# 000018_PGKB_Rev_1_00.net
KiCad netlist of a schematic drawn in EAGLE
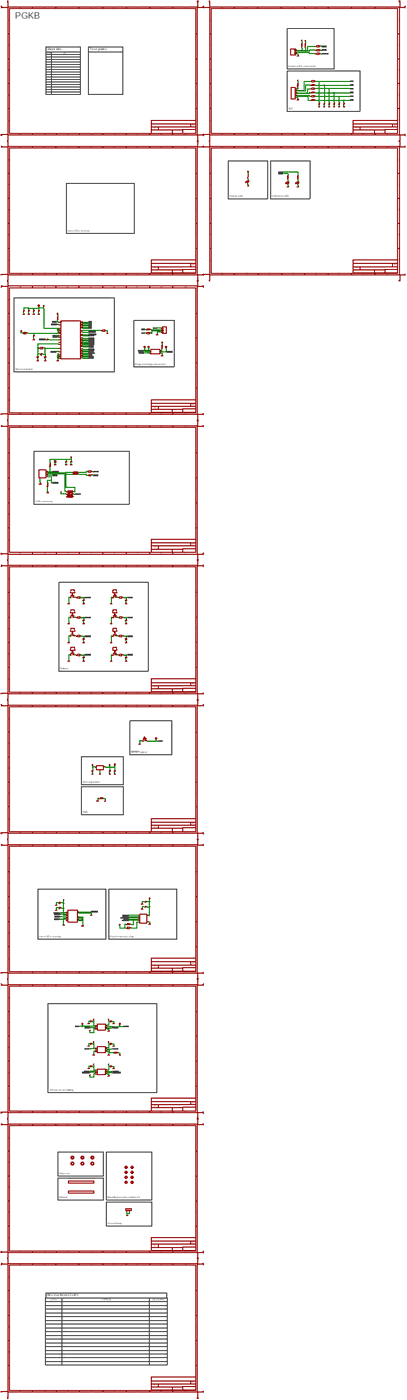
[diagram p0: schematic, sheet 1, overview]
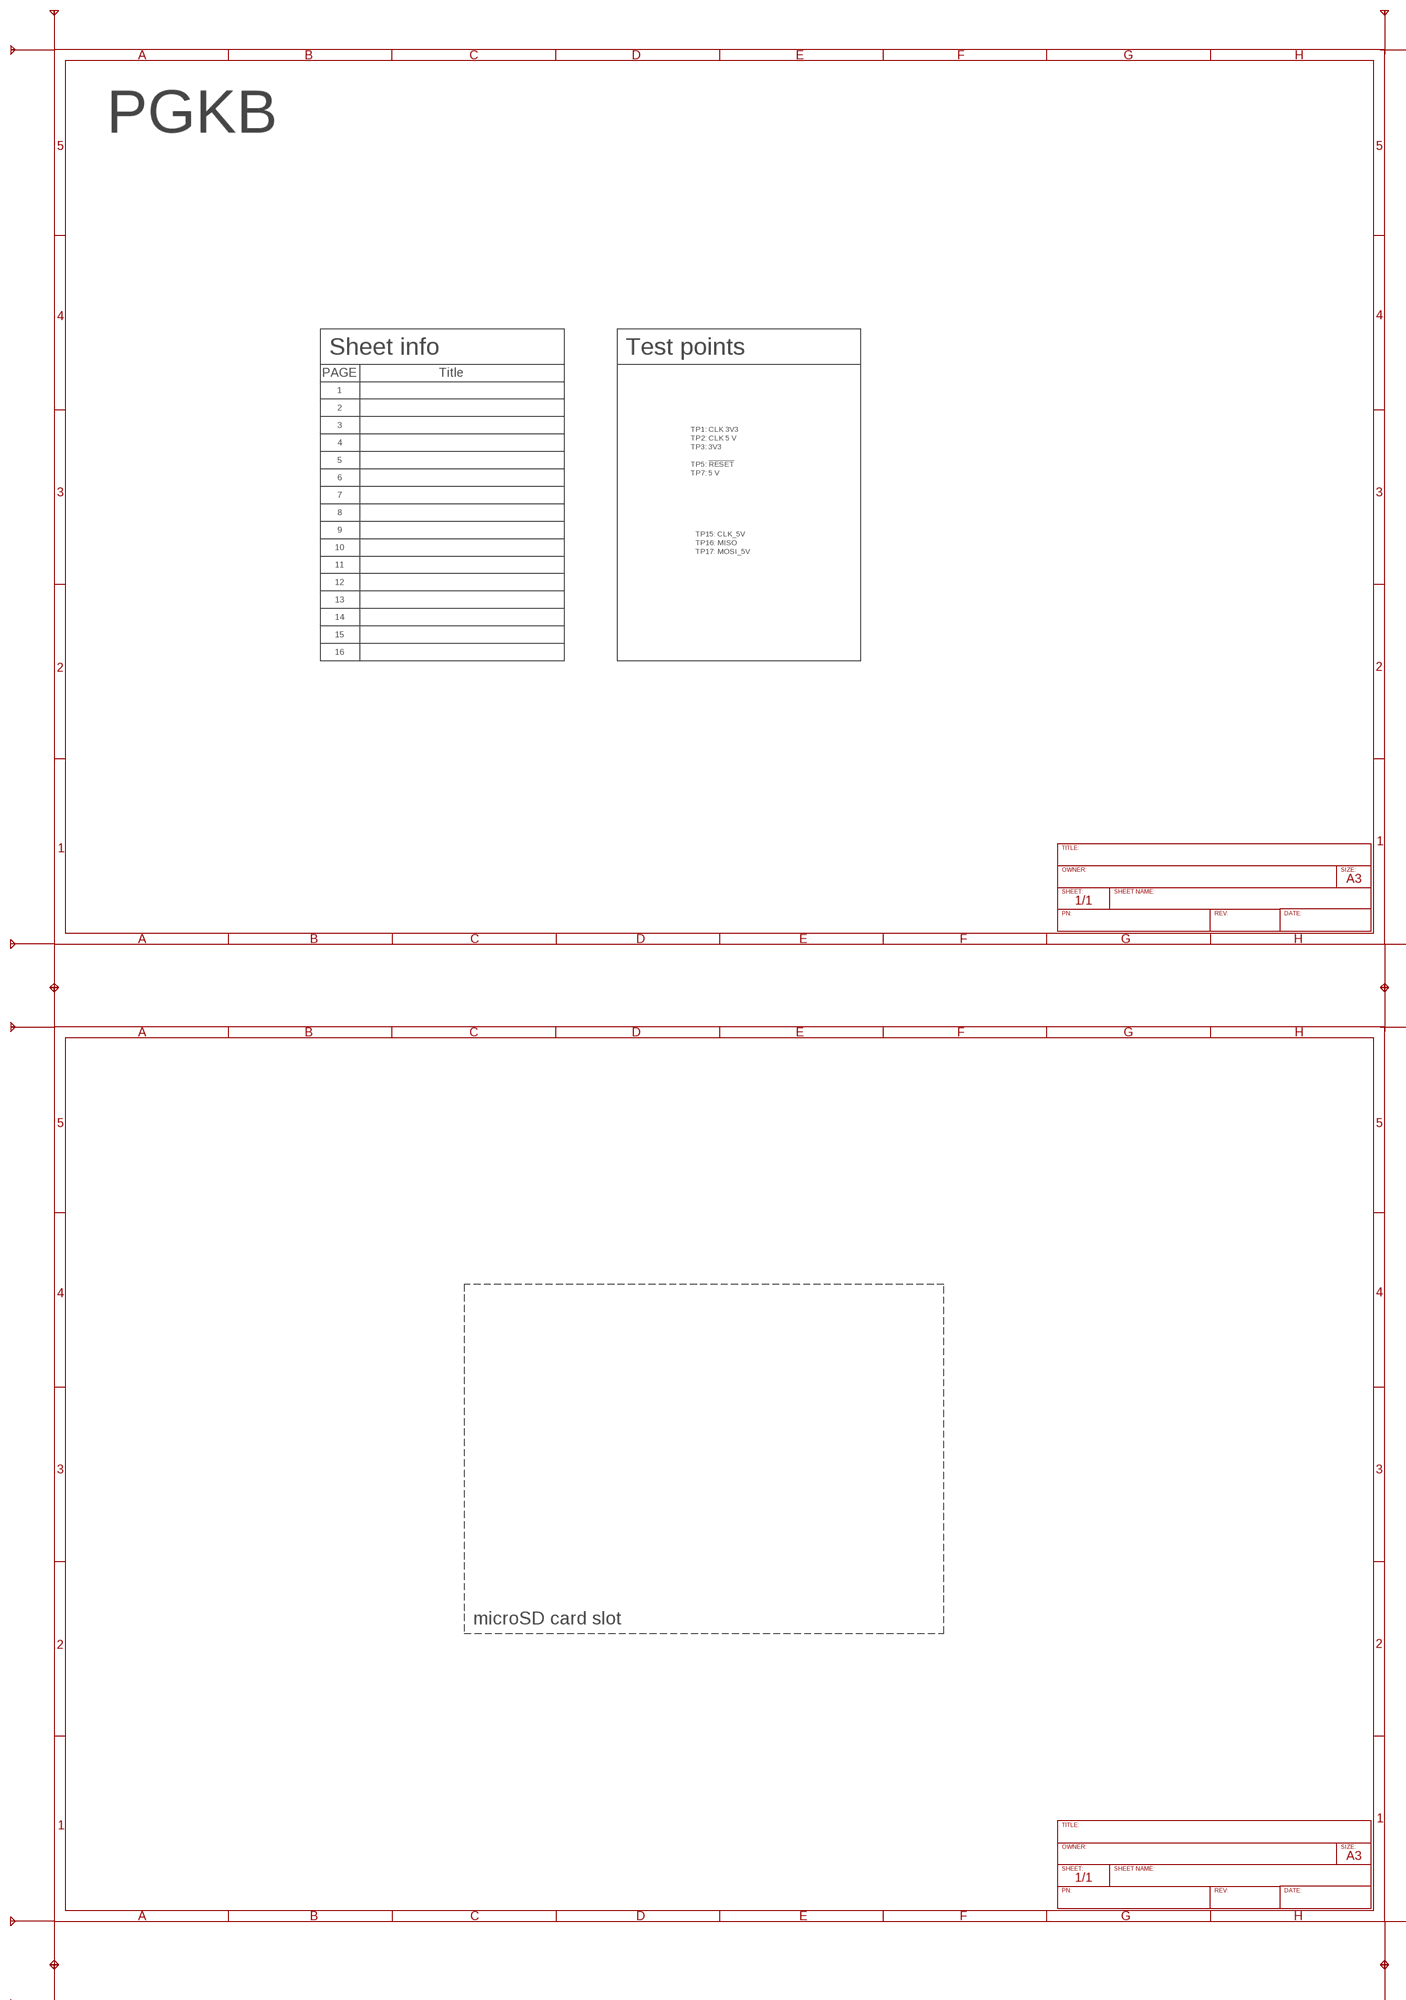
[diagram p1: schematic, sheet 1, part 1 of 7]
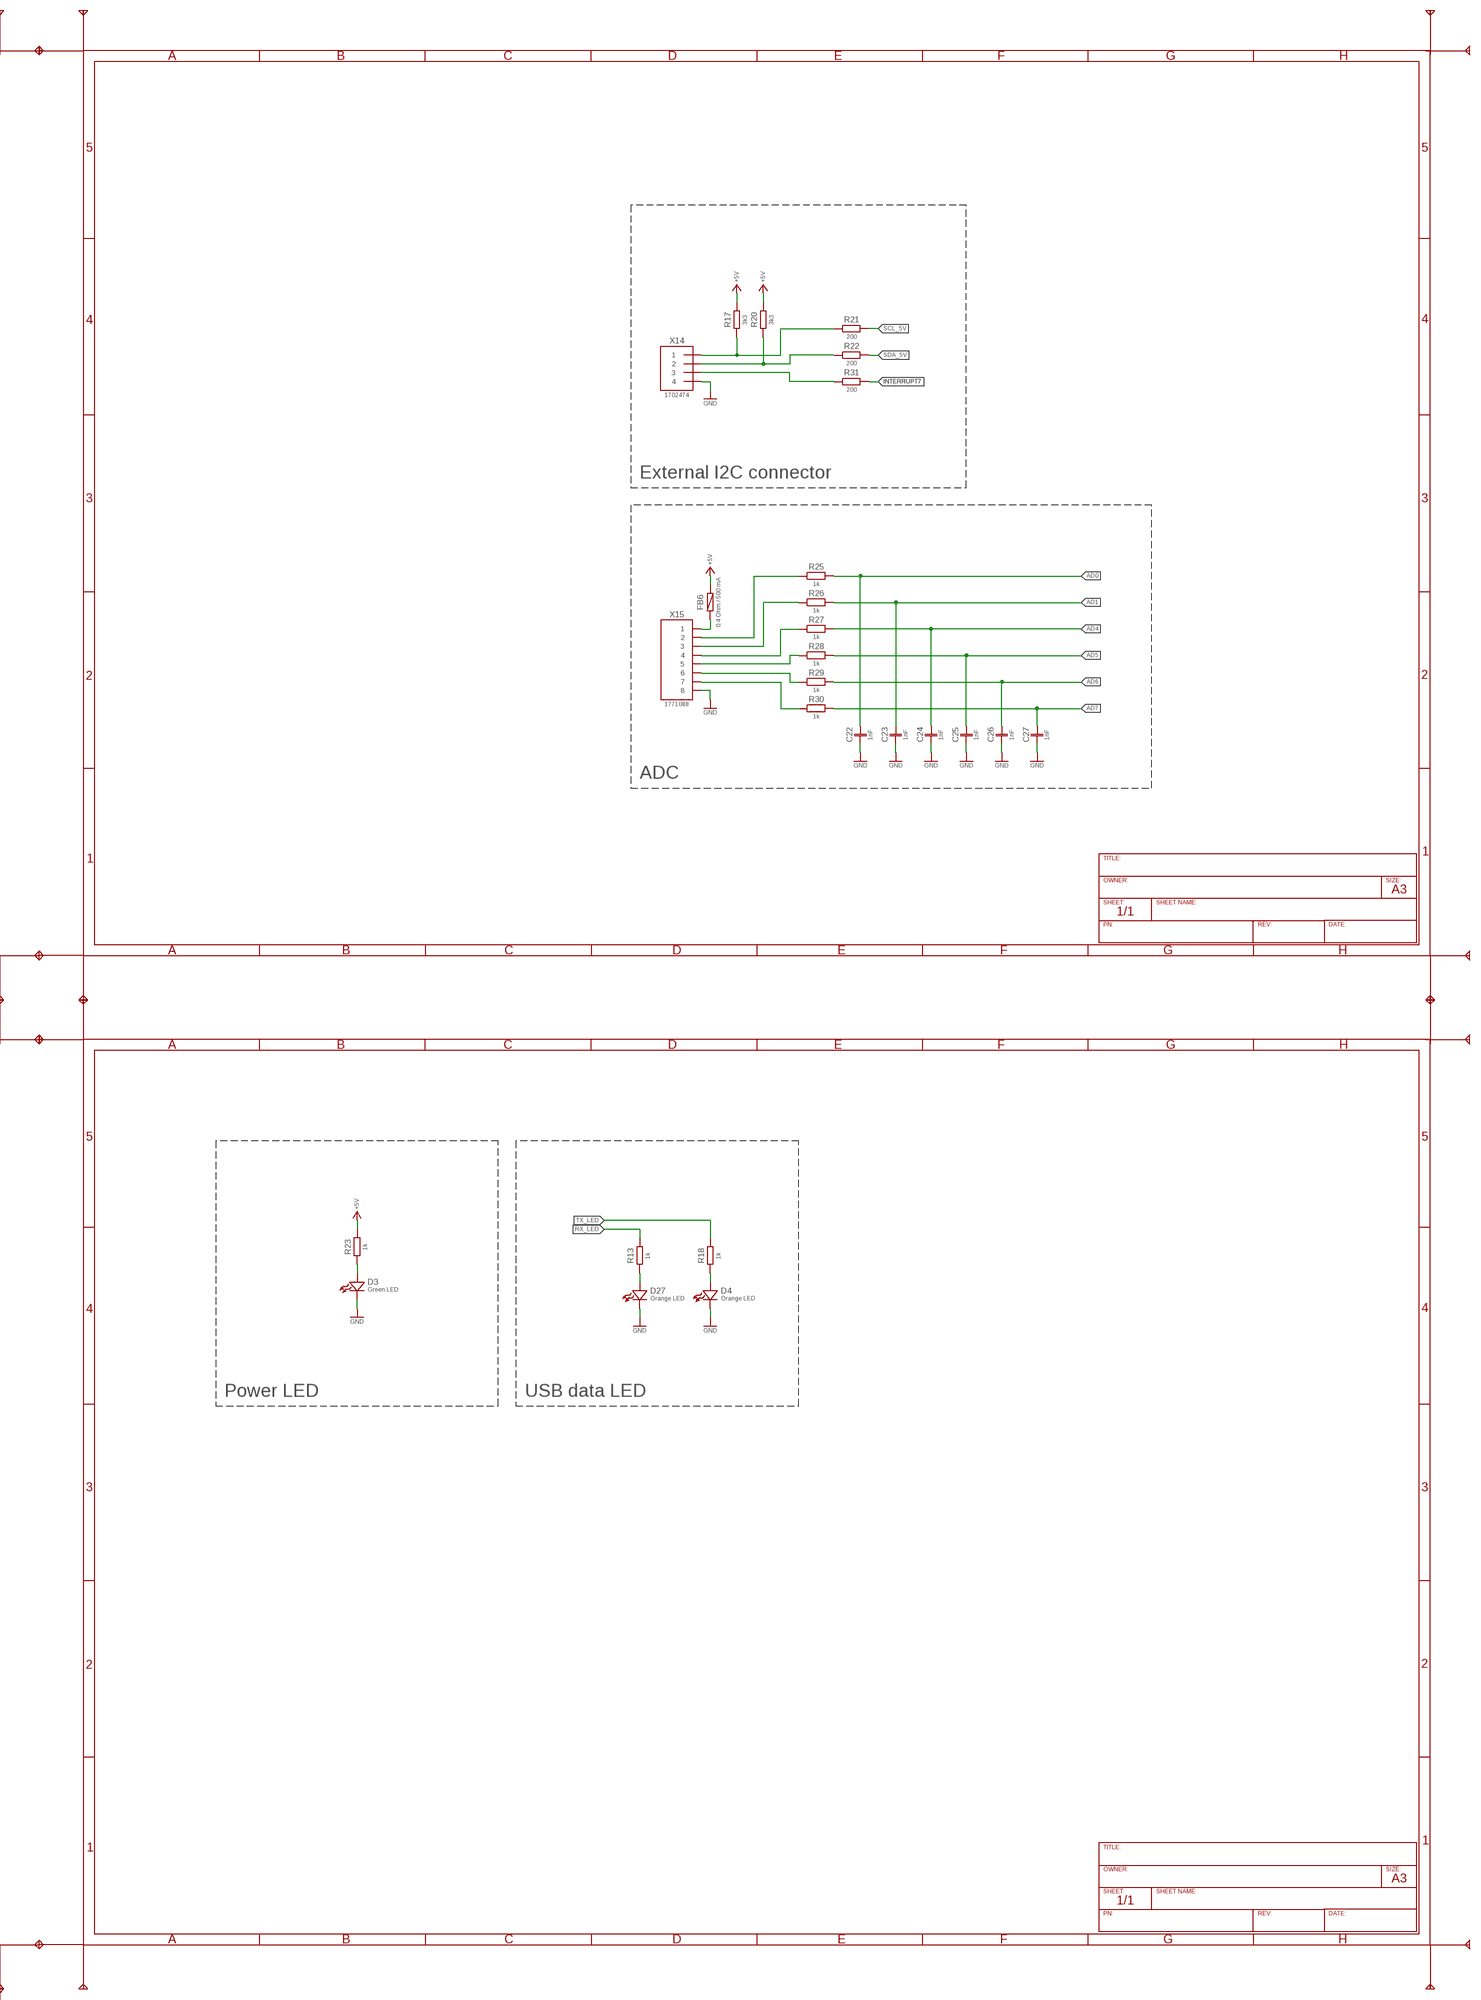
[diagram p2: schematic, sheet 1, part 2 of 7]
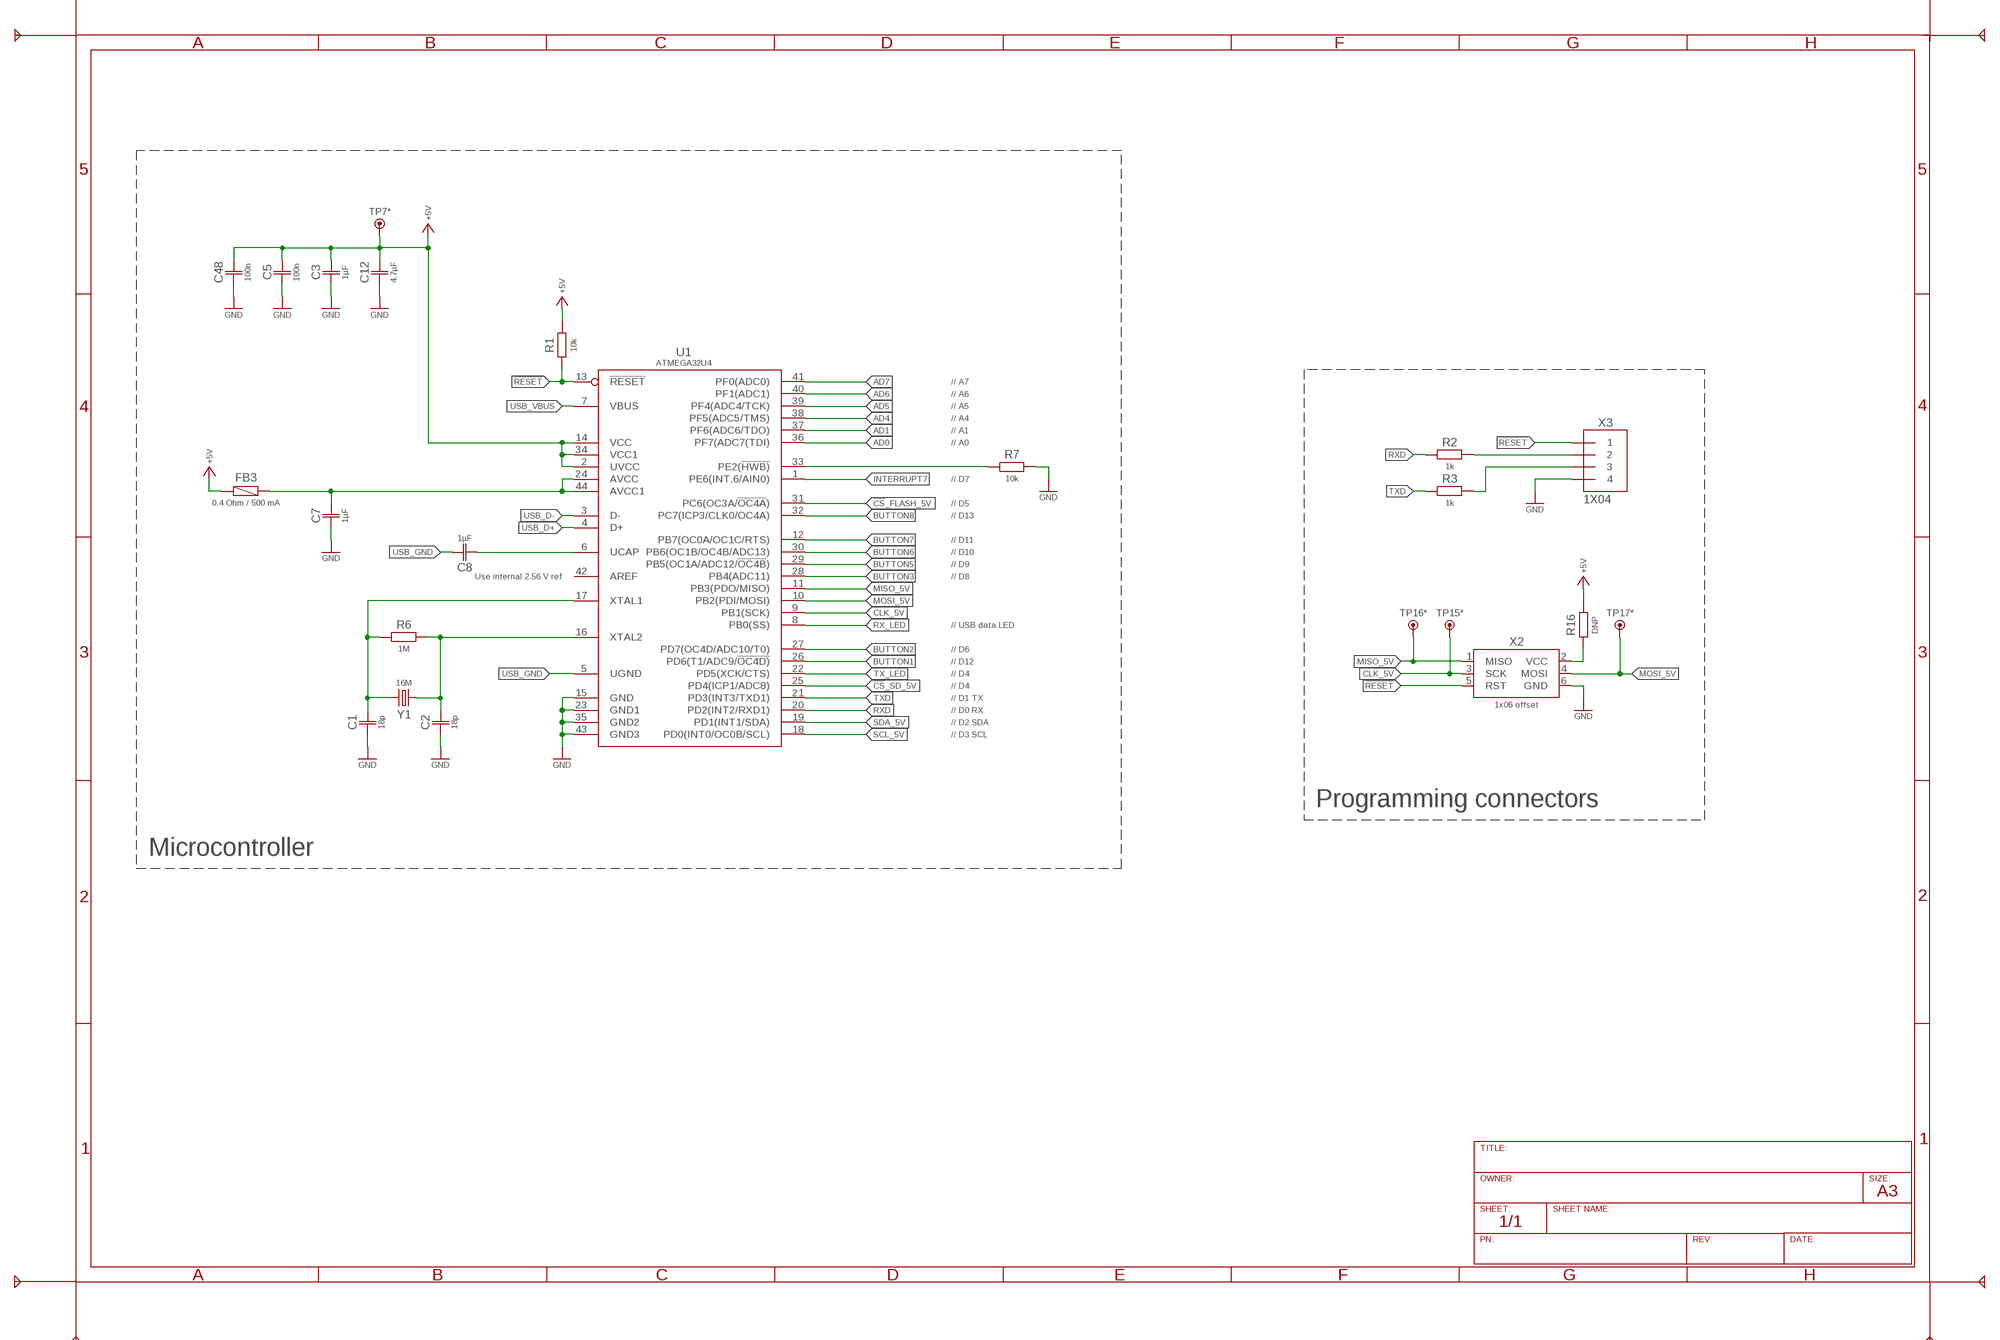
[diagram p3: schematic, sheet 1, part 3 of 7]
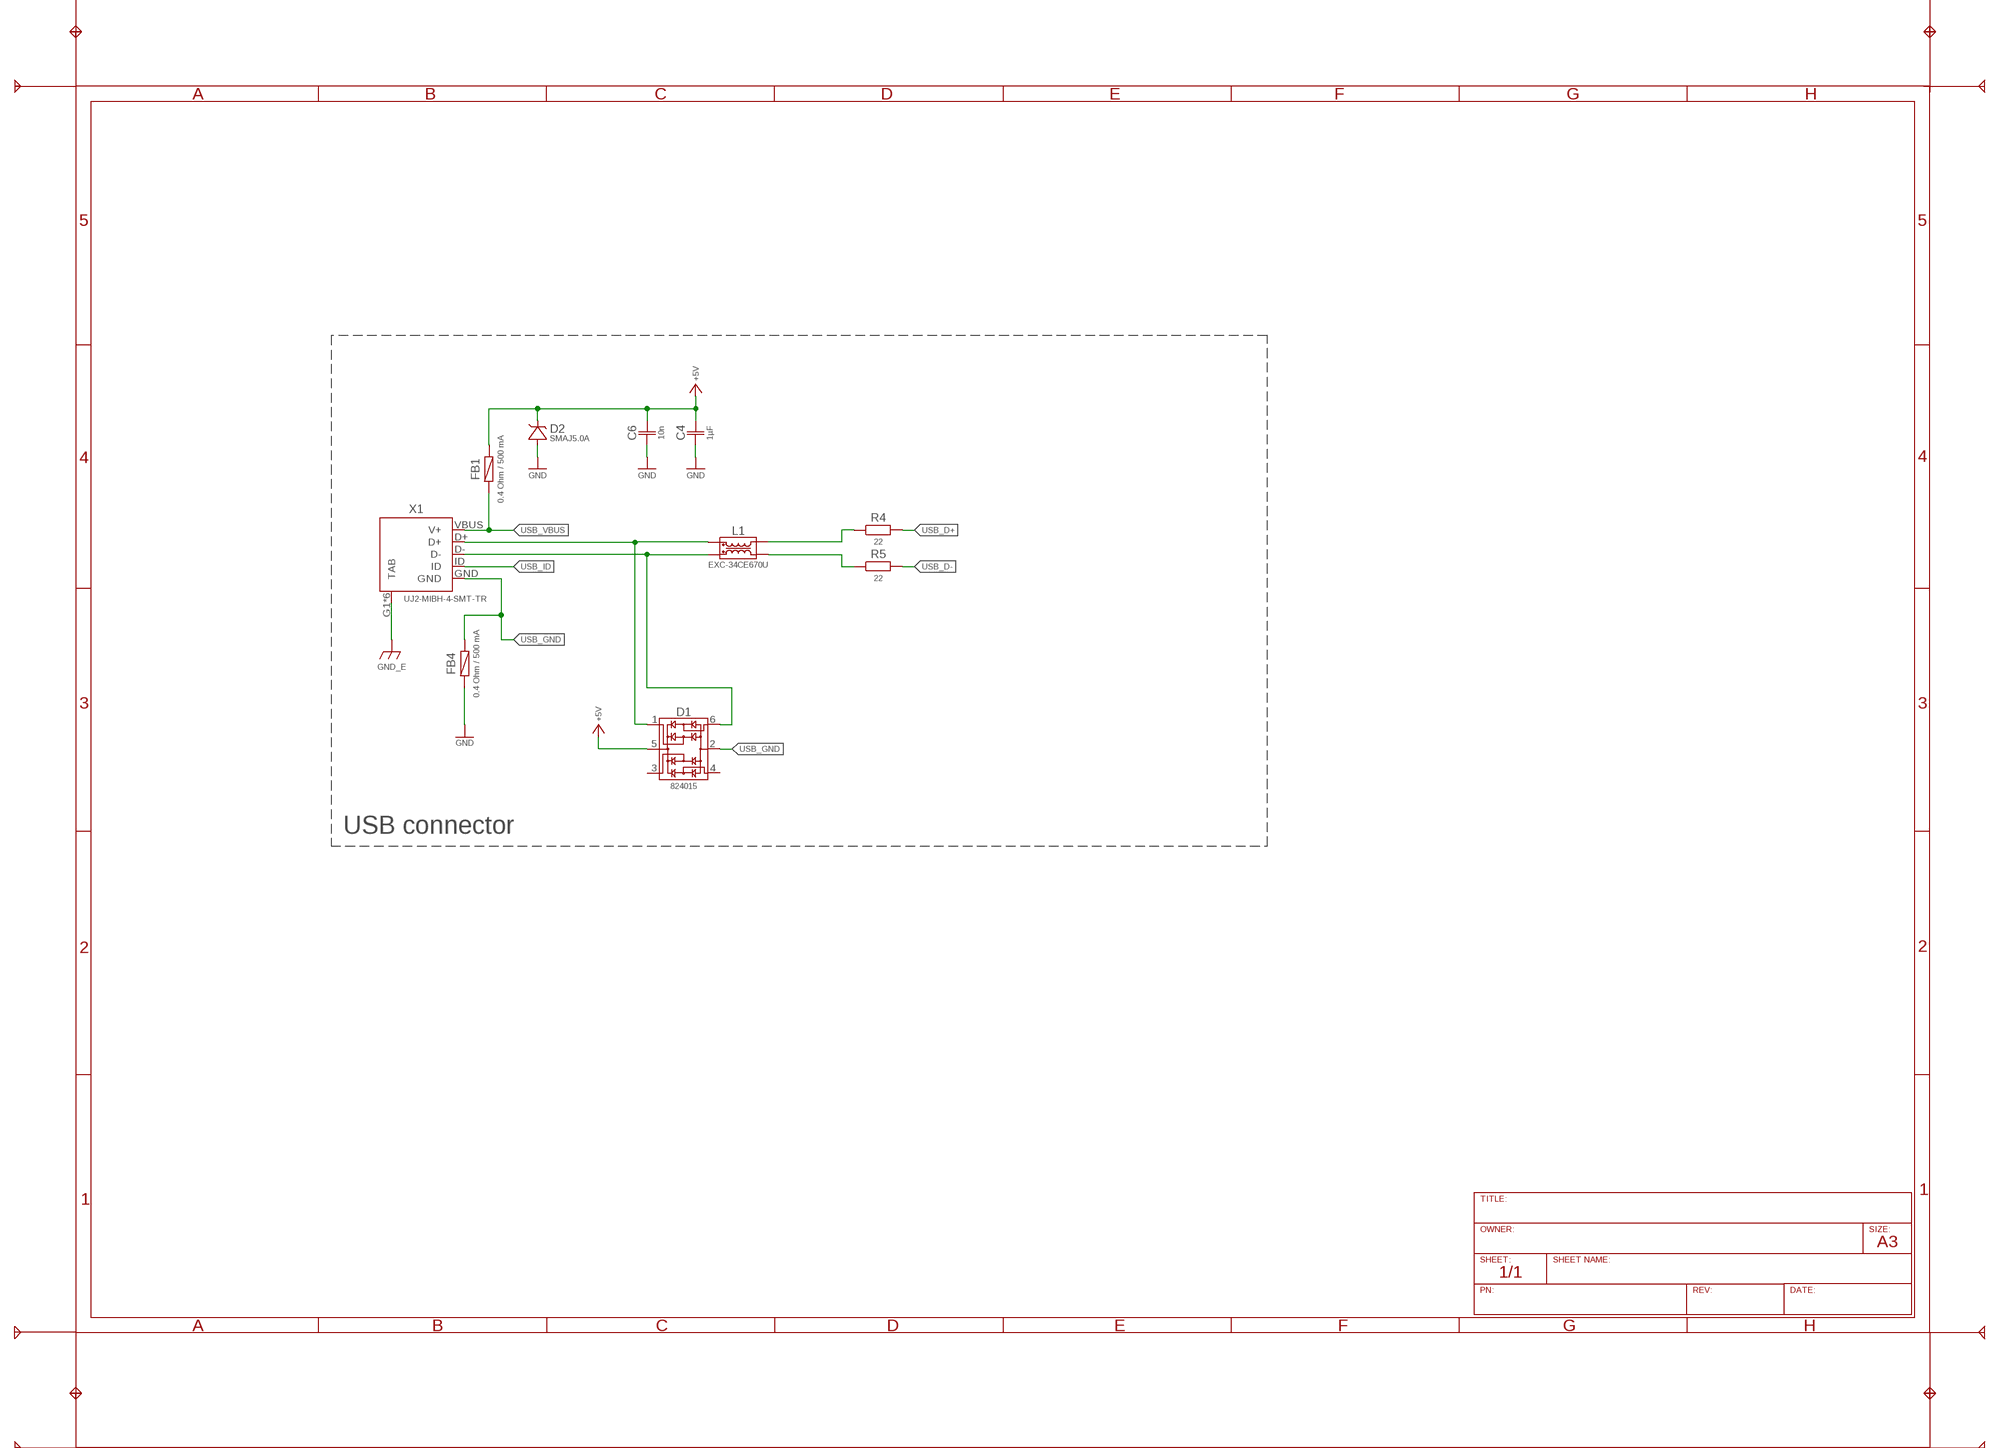
[diagram p4: schematic, sheet 1, part 4 of 7]
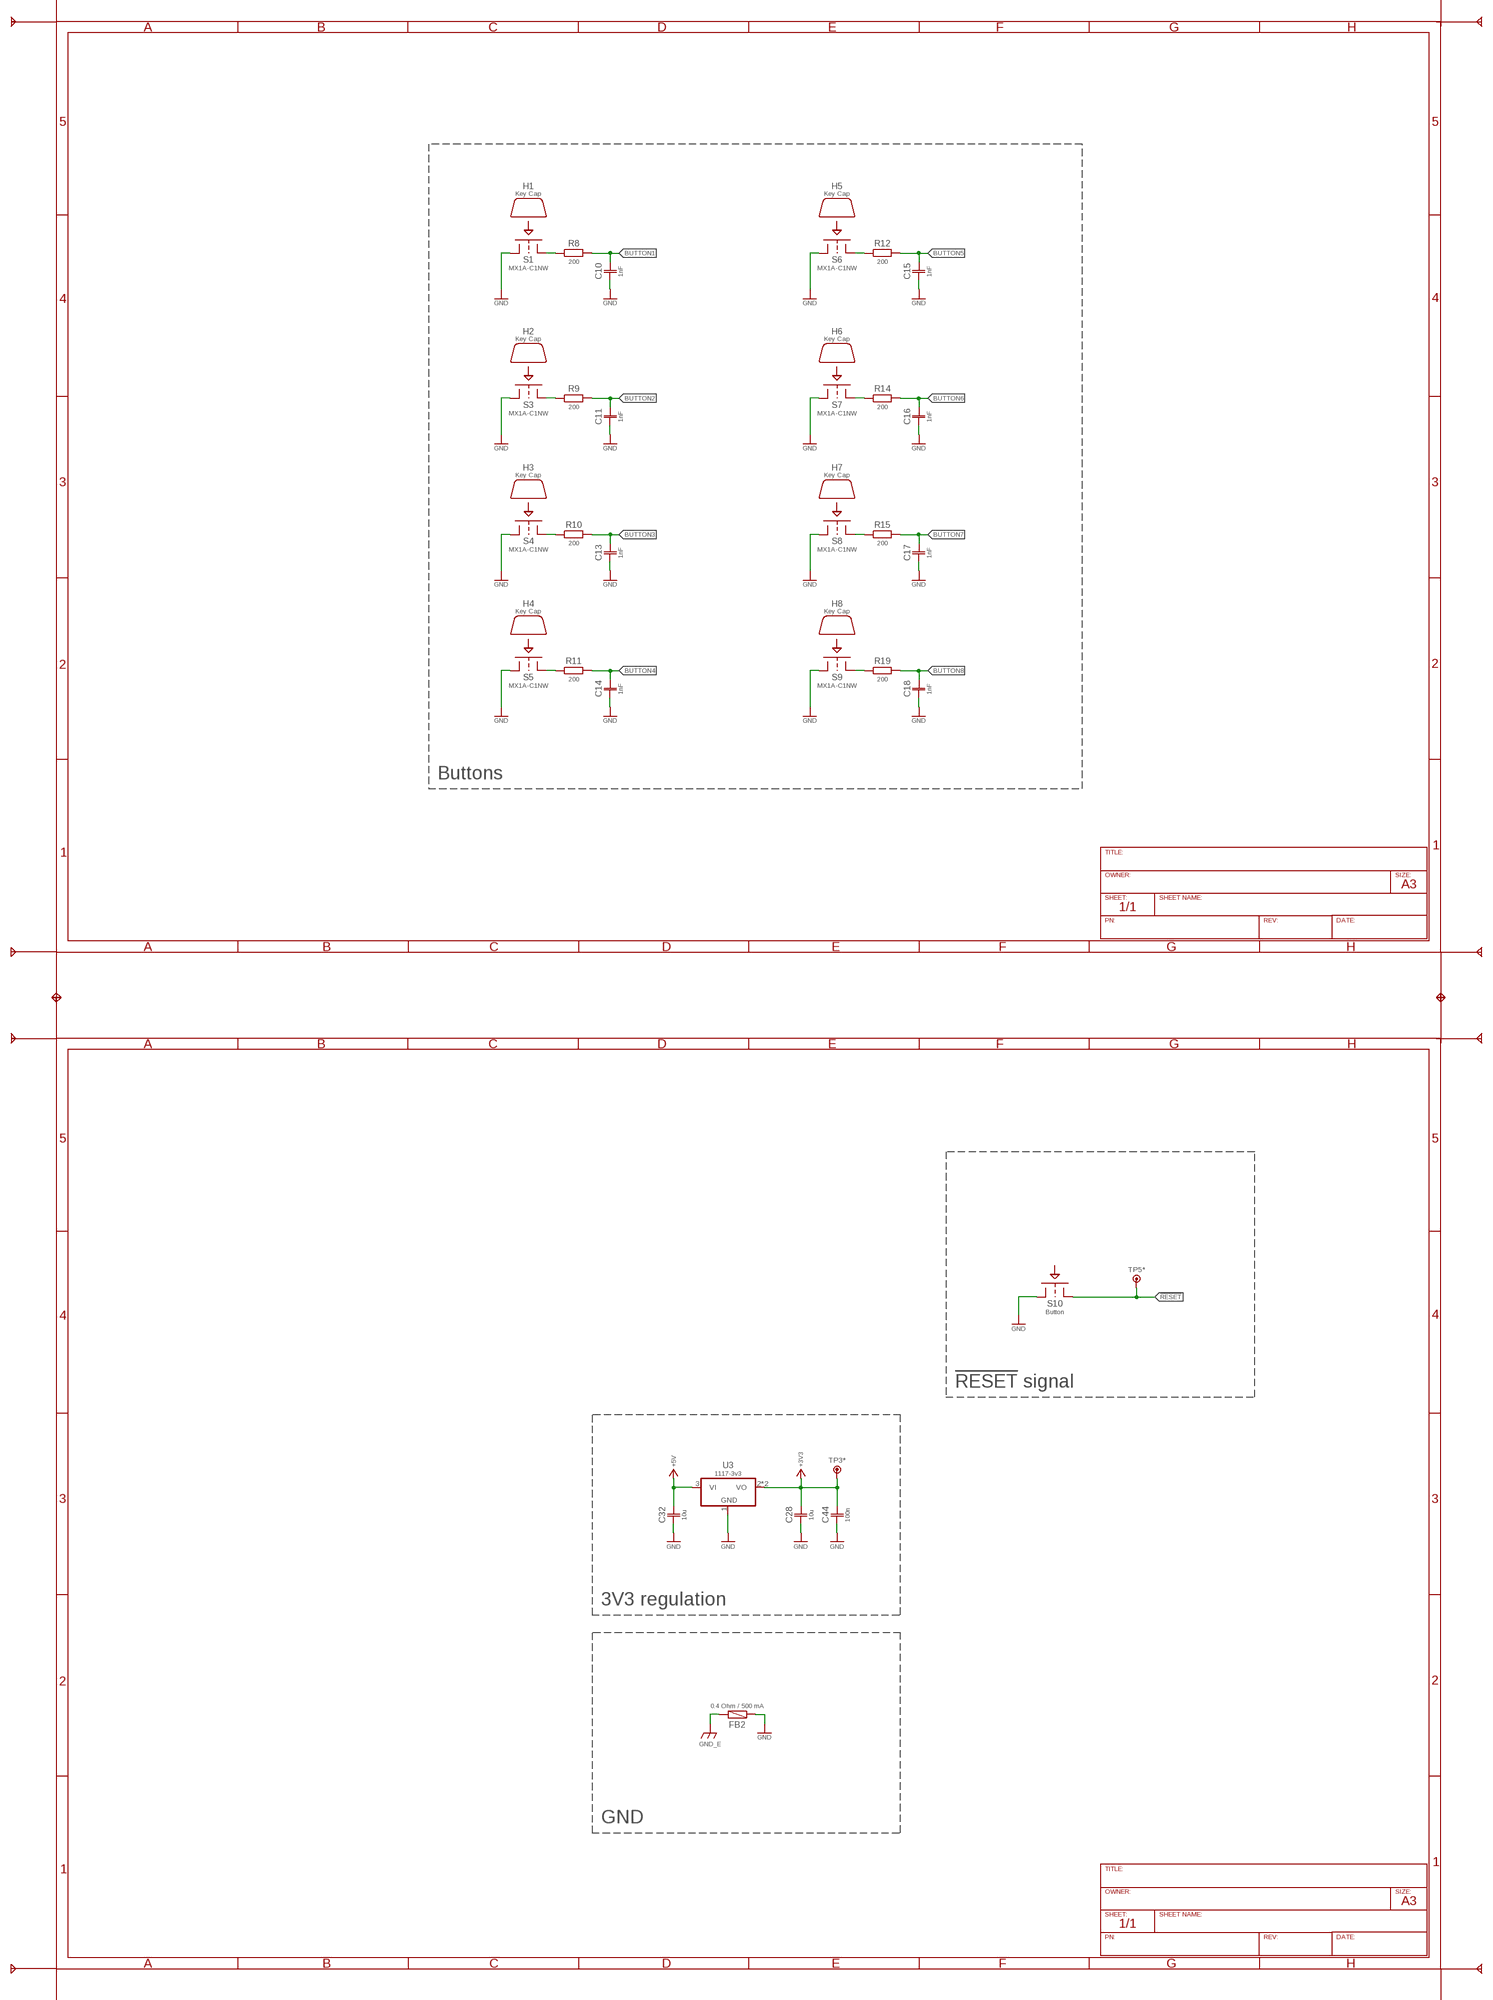
[diagram p5: schematic, sheet 1, part 5 of 7]
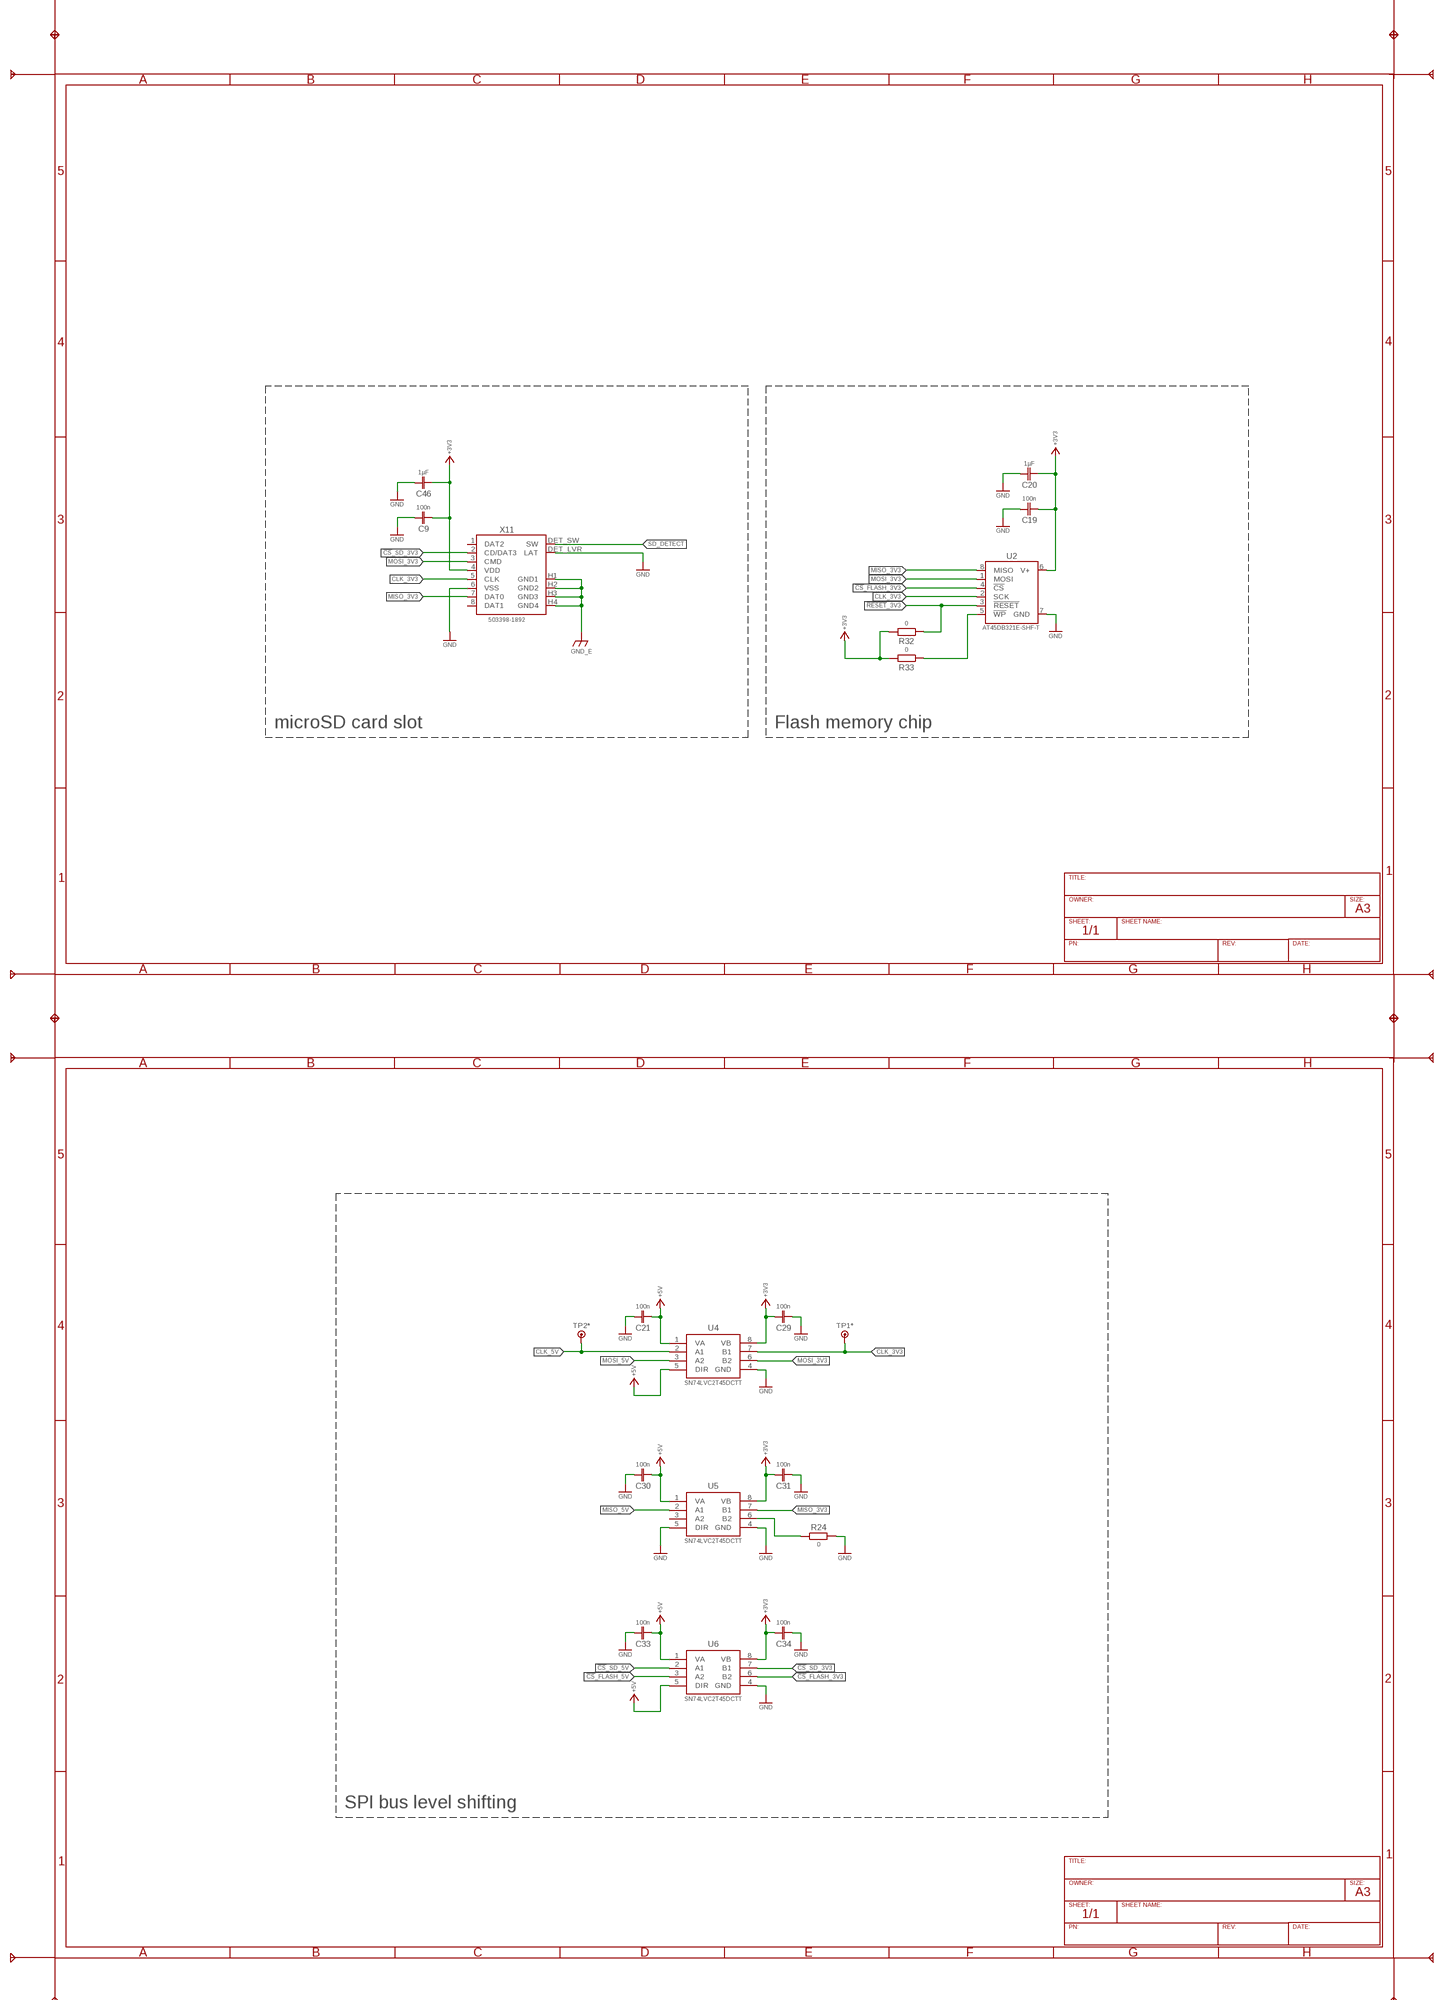
[diagram p6: schematic, sheet 1, part 6 of 7]
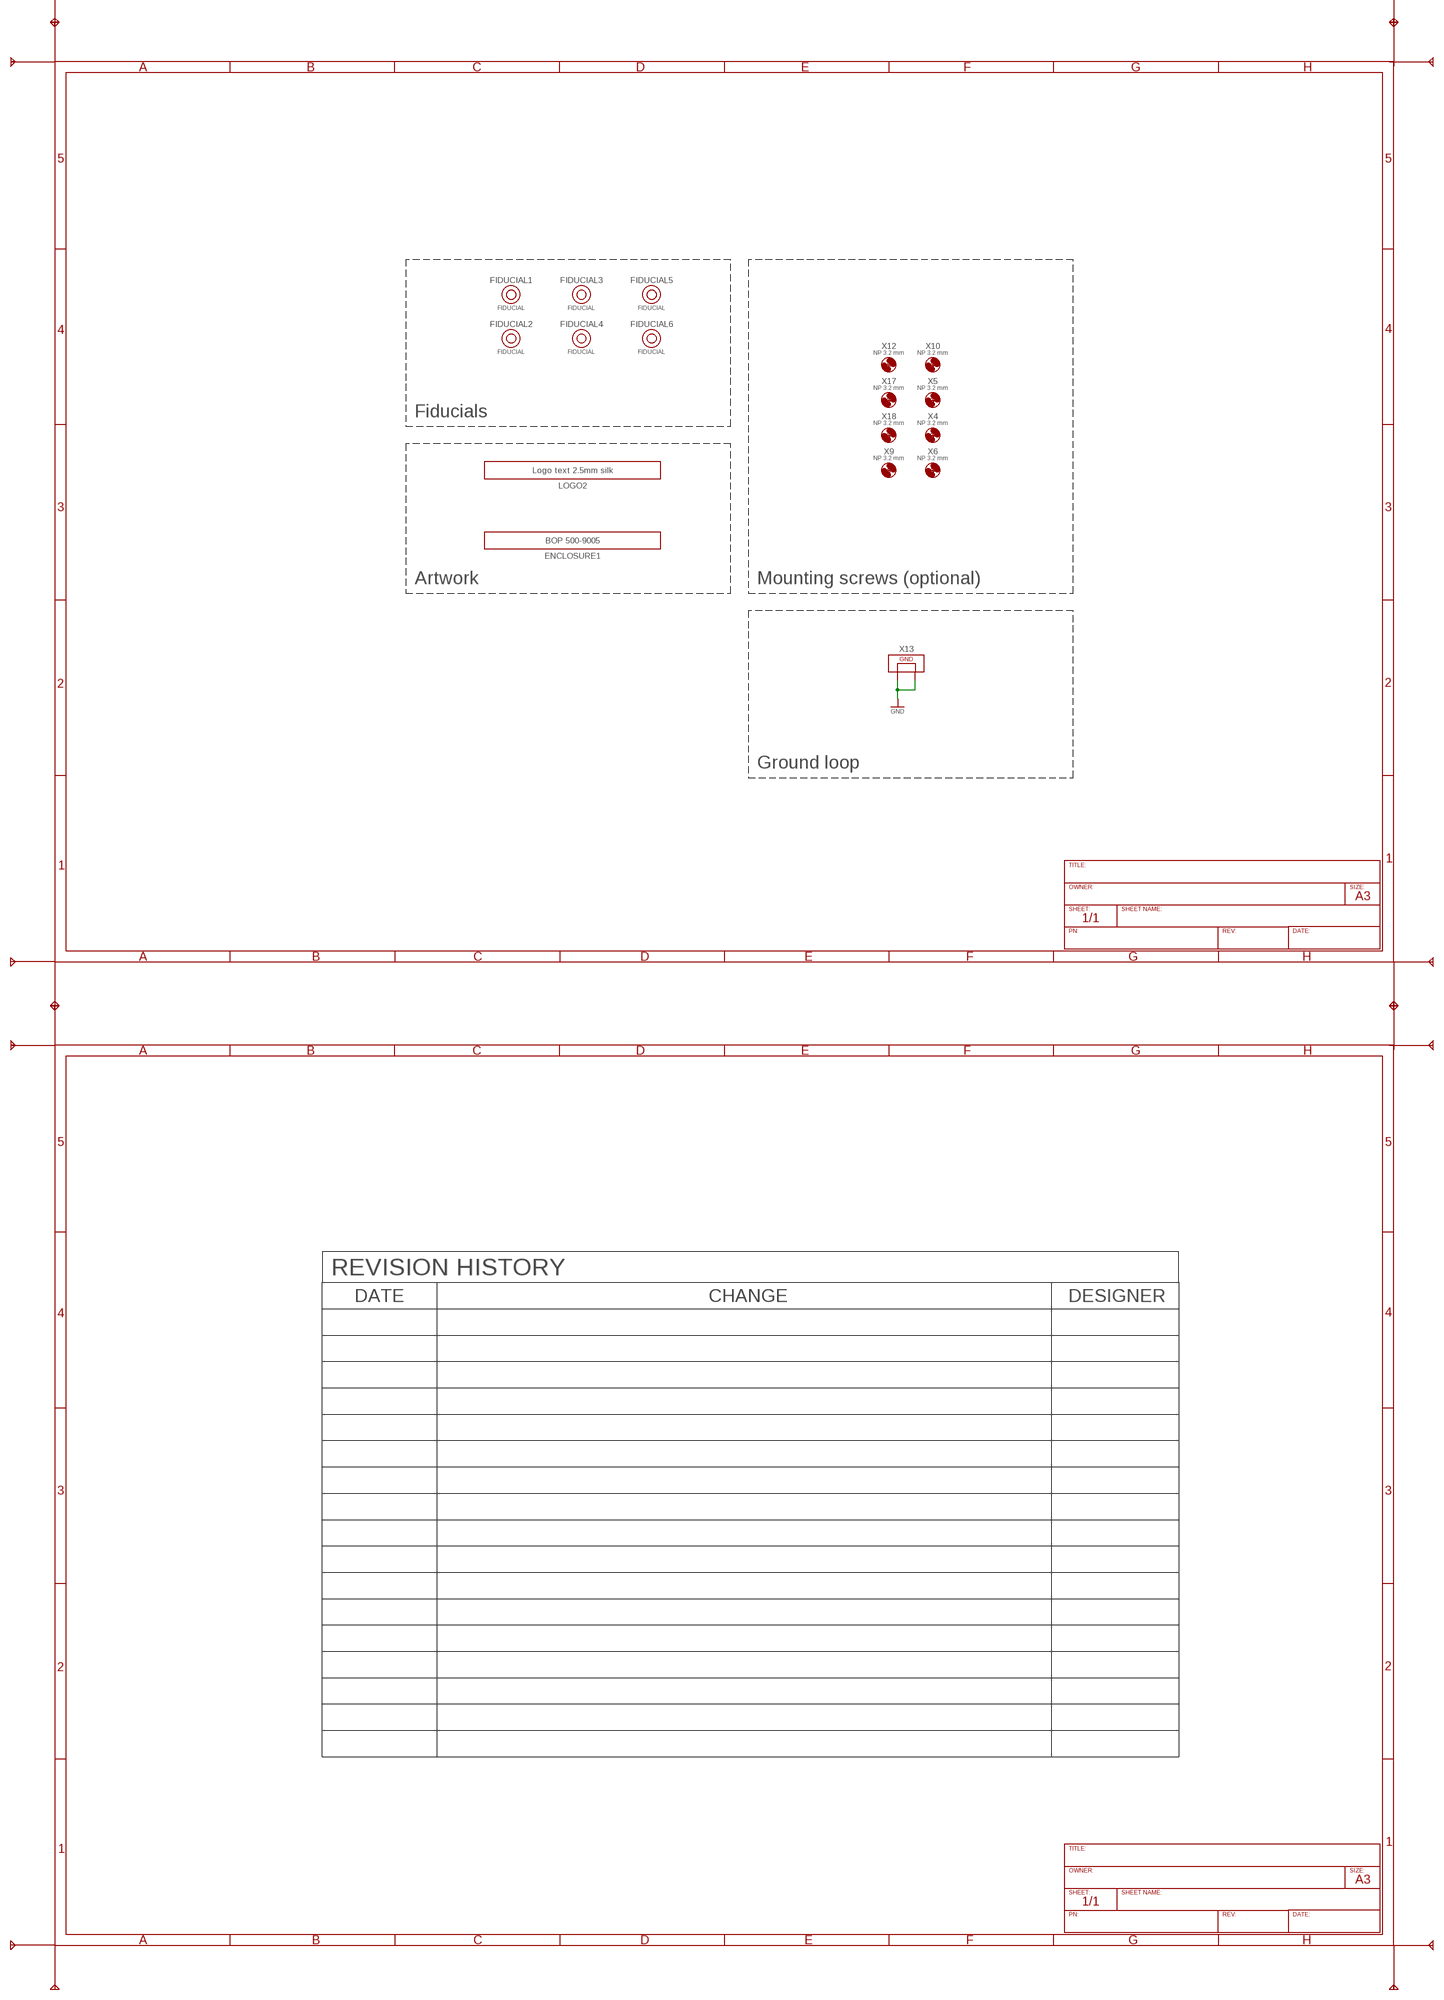
[diagram p7: schematic, sheet 1, part 7 of 7]

(export (version "E")
  (design (tool "Eeschema 10.0.6"))
  (components
    (comp (ref "C1")
      (value "C0805_18PF_50V_NP0")
      (footprint "eagle-import:CAPC2012X160")
      (fields
        (field (name "CODE") "18p")
        (field (name "MANUFACTURER") "Samsung")
        (field (name "MFG_PARTNO") "CL21C180JBANNNC")
      )
      (libsource (lib "eagle-import") (part "C0805_18PF_50V_NP0"))
    )
    (comp (ref "C2")
      (value "C0805_18PF_50V_NP0")
      (footprint "eagle-import:CAPC2012X160")
      (fields
        (field (name "CODE") "18p")
        (field (name "MANUFACTURER") "Samsung")
        (field (name "MFG_PARTNO") "CL21C180JBANNNC")
      )
      (libsource (lib "eagle-import") (part "C0805_18PF_50V_NP0"))
    )
    (comp (ref "C3")
      (value "C0805_1UF_50V_X5R")
      (footprint "eagle-import:CAPC2012X160")
      (fields
        (field (name "CODE") "1µF")
        (field (name "MANUFACTURER") "Murata")
        (field (name "MFG_PARTNO") "GRM219R61H105KA73D")
      )
      (libsource (lib "eagle-import") (part "C0805_1UF_50V_X5R"))
    )
    (comp (ref "C4")
      (value "C0805_1UF_50V_X5R")
      (footprint "eagle-import:CAPC2012X160")
      (fields
        (field (name "CODE") "1µF")
        (field (name "MANUFACTURER") "Murata")
        (field (name "MFG_PARTNO") "GRM219R61H105KA73D")
      )
      (libsource (lib "eagle-import") (part "C0805_1UF_50V_X5R"))
    )
    (comp (ref "C5")
      (value "C0603_100NF_50V_X7R")
      (footprint "eagle-import:CAPC1608X90")
      (fields
        (field (name "CODE") "100n")
        (field (name "MANUFACTURER") "Samsung")
        (field (name "MFG_PARTNO") "CL10B104MB8NNNC")
      )
      (libsource (lib "eagle-import") (part "C0603_100NF_50V_X7R"))
    )
    (comp (ref "C6")
      (value "C0805_10NF_50V_X7R")
      (footprint "eagle-import:CAPC2012X160")
      (fields
        (field (name "CODE") "10n")
        (field (name "MANUFACTURER") "Samsung")
        (field (name "MFG_PARTNO") "CL21B103KBANNNC")
      )
      (libsource (lib "eagle-import") (part "C0805_10NF_50V_X7R"))
    )
    (comp (ref "C7")
      (value "C0805_1UF_50V_X5R")
      (footprint "eagle-import:CAPC2012X160")
      (fields
        (field (name "CODE") "1µF")
        (field (name "MANUFACTURER") "Murata")
        (field (name "MFG_PARTNO") "GRM219R61H105KA73D")
      )
      (libsource (lib "eagle-import") (part "C0805_1UF_50V_X5R"))
    )
    (comp (ref "C8")
      (value "C0805_1UF_50V_X5R")
      (footprint "eagle-import:CAPC2012X160")
      (fields
        (field (name "CODE") "1µF")
        (field (name "MANUFACTURER") "Murata")
        (field (name "MFG_PARTNO") "GRM219R61H105KA73D")
      )
      (libsource (lib "eagle-import") (part "C0805_1UF_50V_X5R"))
    )
    (comp (ref "C9")
      (value "C0603_100NF_50V_X7R")
      (footprint "eagle-import:CAPC1608X90")
      (fields
        (field (name "CODE") "100n")
        (field (name "MANUFACTURER") "Samsung")
        (field (name "MFG_PARTNO") "CL10B104MB8NNNC")
      )
      (libsource (lib "eagle-import") (part "C0603_100NF_50V_X7R"))
    )
    (comp (ref "C10")
      (value "C0805_1NF_50V_X7R")
      (footprint "eagle-import:CAPC2012X160")
      (fields
        (field (name "CODE") "1nF")
        (field (name "MANUFACTURER") "Kemet")
        (field (name "MFG_PARTNO") "C0805C102K5RACTU")
      )
      (libsource (lib "eagle-import") (part "C0805_1NF_50V_X7R"))
    )
    (comp (ref "C11")
      (value "C0805_1NF_50V_X7R")
      (footprint "eagle-import:CAPC2012X160")
      (fields
        (field (name "CODE") "1nF")
        (field (name "MANUFACTURER") "Kemet")
        (field (name "MFG_PARTNO") "C0805C102K5RACTU")
      )
      (libsource (lib "eagle-import") (part "C0805_1NF_50V_X7R"))
    )
    (comp (ref "C12")
      (value "C0805_4.7UF_25V_X5R")
      (footprint "eagle-import:CAPC2012X160")
      (fields
        (field (name "CODE") "4.7µF")
        (field (name "MANUFACTURER") "Samsung")
        (field (name "MFG_PARTNO") "CL21A475KAQNNNG")
      )
      (libsource (lib "eagle-import") (part "C0805_4.7UF_25V_X5R"))
    )
    (comp (ref "C13")
      (value "C0805_1NF_50V_X7R")
      (footprint "eagle-import:CAPC2012X160")
      (fields
        (field (name "CODE") "1nF")
        (field (name "MANUFACTURER") "Kemet")
        (field (name "MFG_PARTNO") "C0805C102K5RACTU")
      )
      (libsource (lib "eagle-import") (part "C0805_1NF_50V_X7R"))
    )
    (comp (ref "C14")
      (value "C0805_1NF_50V_X7R")
      (footprint "eagle-import:CAPC2012X160")
      (fields
        (field (name "CODE") "1nF")
        (field (name "MANUFACTURER") "Kemet")
        (field (name "MFG_PARTNO") "C0805C102K5RACTU")
      )
      (libsource (lib "eagle-import") (part "C0805_1NF_50V_X7R"))
    )
    (comp (ref "C15")
      (value "C0805_1NF_50V_X7R")
      (footprint "eagle-import:CAPC2012X160")
      (fields
        (field (name "CODE") "1nF")
        (field (name "MANUFACTURER") "Kemet")
        (field (name "MFG_PARTNO") "C0805C102K5RACTU")
      )
      (libsource (lib "eagle-import") (part "C0805_1NF_50V_X7R"))
    )
    (comp (ref "C16")
      (value "C0805_1NF_50V_X7R")
      (footprint "eagle-import:CAPC2012X160")
      (fields
        (field (name "CODE") "1nF")
        (field (name "MANUFACTURER") "Kemet")
        (field (name "MFG_PARTNO") "C0805C102K5RACTU")
      )
      (libsource (lib "eagle-import") (part "C0805_1NF_50V_X7R"))
    )
    (comp (ref "C17")
      (value "C0805_1NF_50V_X7R")
      (footprint "eagle-import:CAPC2012X160")
      (fields
        (field (name "CODE") "1nF")
        (field (name "MANUFACTURER") "Kemet")
        (field (name "MFG_PARTNO") "C0805C102K5RACTU")
      )
      (libsource (lib "eagle-import") (part "C0805_1NF_50V_X7R"))
    )
    (comp (ref "C18")
      (value "C0805_1NF_50V_X7R")
      (footprint "eagle-import:CAPC2012X160")
      (fields
        (field (name "CODE") "1nF")
        (field (name "MANUFACTURER") "Kemet")
        (field (name "MFG_PARTNO") "C0805C102K5RACTU")
      )
      (libsource (lib "eagle-import") (part "C0805_1NF_50V_X7R"))
    )
    (comp (ref "C19")
      (value "C0603_100NF_50V_X7R")
      (footprint "eagle-import:CAPC1608X90")
      (fields
        (field (name "CODE") "100n")
        (field (name "MANUFACTURER") "Samsung")
        (field (name "MFG_PARTNO") "CL10B104MB8NNNC")
      )
      (libsource (lib "eagle-import") (part "C0603_100NF_50V_X7R"))
    )
    (comp (ref "C20")
      (value "C0805_1UF_50V_X5R")
      (footprint "eagle-import:CAPC2012X160")
      (fields
        (field (name "CODE") "1µF")
        (field (name "MANUFACTURER") "Murata")
        (field (name "MFG_PARTNO") "GRM219R61H105KA73D")
      )
      (libsource (lib "eagle-import") (part "C0805_1UF_50V_X5R"))
    )
    (comp (ref "C21")
      (value "C0603_100NF_50V_X7R")
      (footprint "eagle-import:CAPC1608X90")
      (fields
        (field (name "CODE") "100n")
        (field (name "MANUFACTURER") "Samsung")
        (field (name "MFG_PARTNO") "CL10B104MB8NNNC")
      )
      (libsource (lib "eagle-import") (part "C0603_100NF_50V_X7R"))
    )
    (comp (ref "C22")
      (value "C0805_1NF_50V_X7R")
      (footprint "eagle-import:CAPC2012X160")
      (fields
        (field (name "CODE") "1nF")
        (field (name "MANUFACTURER") "Kemet")
        (field (name "MFG_PARTNO") "C0805C102K5RACTU")
      )
      (libsource (lib "eagle-import") (part "C0805_1NF_50V_X7R"))
    )
    (comp (ref "C23")
      (value "C0805_1NF_50V_X7R")
      (footprint "eagle-import:CAPC2012X160")
      (fields
        (field (name "CODE") "1nF")
        (field (name "MANUFACTURER") "Kemet")
        (field (name "MFG_PARTNO") "C0805C102K5RACTU")
      )
      (libsource (lib "eagle-import") (part "C0805_1NF_50V_X7R"))
    )
    (comp (ref "C24")
      (value "C0805_1NF_50V_X7R")
      (footprint "eagle-import:CAPC2012X160")
      (fields
        (field (name "CODE") "1nF")
        (field (name "MANUFACTURER") "Kemet")
        (field (name "MFG_PARTNO") "C0805C102K5RACTU")
      )
      (libsource (lib "eagle-import") (part "C0805_1NF_50V_X7R"))
    )
    (comp (ref "C25")
      (value "C0805_1NF_50V_X7R")
      (footprint "eagle-import:CAPC2012X160")
      (fields
        (field (name "CODE") "1nF")
        (field (name "MANUFACTURER") "Kemet")
        (field (name "MFG_PARTNO") "C0805C102K5RACTU")
      )
      (libsource (lib "eagle-import") (part "C0805_1NF_50V_X7R"))
    )
    (comp (ref "C26")
      (value "C0805_1NF_50V_X7R")
      (footprint "eagle-import:CAPC2012X160")
      (fields
        (field (name "CODE") "1nF")
        (field (name "MANUFACTURER") "Kemet")
        (field (name "MFG_PARTNO") "C0805C102K5RACTU")
      )
      (libsource (lib "eagle-import") (part "C0805_1NF_50V_X7R"))
    )
    (comp (ref "C27")
      (value "C0805_1NF_50V_X7R")
      (footprint "eagle-import:CAPC2012X160")
      (fields
        (field (name "CODE") "1nF")
        (field (name "MANUFACTURER") "Kemet")
        (field (name "MFG_PARTNO") "C0805C102K5RACTU")
      )
      (libsource (lib "eagle-import") (part "C0805_1NF_50V_X7R"))
    )
    (comp (ref "C28")
      (value "C1206_10UF_16V_Y5V")
      (footprint "eagle-import:CAPC3216X200")
      (fields
        (field (name "CODE") "10u")
        (field (name "MANUFACTURER") "Yageo")
        (field (name "MFG_PARTNO") "CC1206ZKY5V7BB106")
      )
      (libsource (lib "eagle-import") (part "C1206_10UF_16V_Y5V"))
    )
    (comp (ref "C29")
      (value "C0603_100NF_50V_X7R")
      (footprint "eagle-import:CAPC1608X90")
      (fields
        (field (name "CODE") "100n")
        (field (name "MANUFACTURER") "Samsung")
        (field (name "MFG_PARTNO") "CL10B104MB8NNNC")
      )
      (libsource (lib "eagle-import") (part "C0603_100NF_50V_X7R"))
    )
    (comp (ref "C30")
      (value "C0603_100NF_50V_X7R")
      (footprint "eagle-import:CAPC1608X90")
      (fields
        (field (name "CODE") "100n")
        (field (name "MANUFACTURER") "Samsung")
        (field (name "MFG_PARTNO") "CL10B104MB8NNNC")
      )
      (libsource (lib "eagle-import") (part "C0603_100NF_50V_X7R"))
    )
    (comp (ref "C31")
      (value "C0603_100NF_50V_X7R")
      (footprint "eagle-import:CAPC1608X90")
      (fields
        (field (name "CODE") "100n")
        (field (name "MANUFACTURER") "Samsung")
        (field (name "MFG_PARTNO") "CL10B104MB8NNNC")
      )
      (libsource (lib "eagle-import") (part "C0603_100NF_50V_X7R"))
    )
    (comp (ref "C32")
      (value "C1206_10UF_16V_Y5V")
      (footprint "eagle-import:CAPC3216X200")
      (fields
        (field (name "CODE") "10u")
        (field (name "MANUFACTURER") "Yageo")
        (field (name "MFG_PARTNO") "CC1206ZKY5V7BB106")
      )
      (libsource (lib "eagle-import") (part "C1206_10UF_16V_Y5V"))
    )
    (comp (ref "C33")
      (value "C0603_100NF_50V_X7R")
      (footprint "eagle-import:CAPC1608X90")
      (fields
        (field (name "CODE") "100n")
        (field (name "MANUFACTURER") "Samsung")
        (field (name "MFG_PARTNO") "CL10B104MB8NNNC")
      )
      (libsource (lib "eagle-import") (part "C0603_100NF_50V_X7R"))
    )
    (comp (ref "C34")
      (value "C0603_100NF_50V_X7R")
      (footprint "eagle-import:CAPC1608X90")
      (fields
        (field (name "CODE") "100n")
        (field (name "MANUFACTURER") "Samsung")
        (field (name "MFG_PARTNO") "CL10B104MB8NNNC")
      )
      (libsource (lib "eagle-import") (part "C0603_100NF_50V_X7R"))
    )
    (comp (ref "C44")
      (value "C0603_100NF_50V_X7R")
      (footprint "eagle-import:CAPC1608X90")
      (fields
        (field (name "CODE") "100n")
        (field (name "MANUFACTURER") "Samsung")
        (field (name "MFG_PARTNO") "CL10B104MB8NNNC")
      )
      (libsource (lib "eagle-import") (part "C0603_100NF_50V_X7R"))
    )
    (comp (ref "C46")
      (value "C0805_1UF_50V_X5R")
      (footprint "eagle-import:CAPC2012X160")
      (fields
        (field (name "CODE") "1µF")
        (field (name "MANUFACTURER") "Murata")
        (field (name "MFG_PARTNO") "GRM219R61H105KA73D")
      )
      (libsource (lib "eagle-import") (part "C0805_1UF_50V_X5R"))
    )
    (comp (ref "C48")
      (value "C0603_100NF_50V_X7R")
      (footprint "eagle-import:CAPC1608X90")
      (fields
        (field (name "CODE") "100n")
        (field (name "MANUFACTURER") "Samsung")
        (field (name "MFG_PARTNO") "CL10B104MB8NNNC")
      )
      (libsource (lib "eagle-import") (part "C0603_100NF_50V_X7R"))
    )
    (comp (ref "D1")
      (value "DIODE_TVS_5V_BI_824015")
      (footprint "eagle-import:SOP95P280X120-6N")
      (fields
        (field (name "CODE") "824015")
        (field (name "MANUFACTURER") "Wurth")
        (field (name "MFG_PARTNO") "824015")
      )
      (libsource (lib "eagle-import") (part "DIODE_TVS_5V_BI_824015"))
    )
    (comp (ref "D2")
      (value "DIODE_TVS_5V_SMAJ5.0A")
      (footprint "eagle-import:DIOC530X280X230_SMA_A")
      (fields
        (field (name "CODE") "SMAJ5.0A")
        (field (name "MANUFACTURER") "Vishay Semiconductor Diodes Division")
        (field (name "MFG_PARTNO") "SMAJ5.0A-E3/61")
      )
      (libsource (lib "eagle-import") (part "DIODE_TVS_5V_SMAJ5.0A"))
    )
    (comp (ref "D3")
      (value "LED_0603_GREEN_CLEAR_APTD1608CGCK")
      (footprint "eagle-import:LEDM1608X80N_DOME")
      (fields
        (field (name "CODE") "Green LED")
        (field (name "MANUFACTURER") "Kingbright")
        (field (name "MFG_PARTNO") "APTD1608CGCK")
      )
      (libsource (lib "eagle-import") (part "LED_0603_GREEN_CLEAR_APTD1608CGCK"))
    )
    (comp (ref "D4")
      (value "LED_0603_AMBER_DIFF_LOQ976-PS-25")
      (footprint "eagle-import:LEDM1608X80N")
      (fields
        (field (name "CODE") "Orange LED")
        (field (name "MANUFACTURER") "OSRAM Opto Semiconductors Inc.")
        (field (name "MFG_PARTNO") "LO Q976-PS-25")
      )
      (libsource (lib "eagle-import") (part "LED_0603_AMBER_DIFF_LOQ976-PS-25"))
    )
    (comp (ref "D27")
      (value "LED_0603_AMBER_DIFF_LOQ976-PS-25")
      (footprint "eagle-import:LEDM1608X80N")
      (fields
        (field (name "CODE") "Orange LED")
        (field (name "MANUFACTURER") "OSRAM Opto Semiconductors Inc.")
        (field (name "MFG_PARTNO") "LO Q976-PS-25")
      )
      (libsource (lib "eagle-import") (part "LED_0603_AMBER_DIFF_LOQ976-PS-25"))
    )
    (comp (ref "ENCLOSURE1")
      (value "ENCLOSURE_BOPLA_BOP-500-9005-TOP")
      (footprint "eagle-import:ENCLOSURE_BOPLA_BOP-500-9005")
      (fields
        (field (name "CODE") "BOP 500-9005")
        (field (name "MANUFACTURER") "BOPLA")
        (field (name "MFG_PARTNO") "BOP 500-9005")
      )
      (libsource (lib "eagle-import") (part "ENCLOSURE_BOPLA_BOP-500-9005-TOP"))
    )
    (comp (ref "FB1")
      (value "FERRITE_0805_0A5")
      (footprint "eagle-import:RESC2012X50")
      (fields
        (field (name "CODE") "0.4 Ohm / 500 mA")
        (field (name "MANUFACTURER") "TDK")
        (field (name "MFG_PARTNO") "MMZ2012Y152B")
      )
      (libsource (lib "eagle-import") (part "FERRITE_0805_0A5"))
    )
    (comp (ref "FB2")
      (value "FERRITE_0805_0A5")
      (footprint "eagle-import:RESC2012X50")
      (fields
        (field (name "CODE") "0.4 Ohm / 500 mA")
        (field (name "MANUFACTURER") "TDK")
        (field (name "MFG_PARTNO") "MMZ2012Y152B")
      )
      (libsource (lib "eagle-import") (part "FERRITE_0805_0A5"))
    )
    (comp (ref "FB3")
      (value "FERRITE_0805_0A5")
      (footprint "eagle-import:RESC2012X50")
      (fields
        (field (name "CODE") "0.4 Ohm / 500 mA")
        (field (name "MANUFACTURER") "TDK")
        (field (name "MFG_PARTNO") "MMZ2012Y152B")
      )
      (libsource (lib "eagle-import") (part "FERRITE_0805_0A5"))
    )
    (comp (ref "FB4")
      (value "FERRITE_0805_0A5")
      (footprint "eagle-import:RESC2012X50")
      (fields
        (field (name "CODE") "0.4 Ohm / 500 mA")
        (field (name "MANUFACTURER") "TDK")
        (field (name "MFG_PARTNO") "MMZ2012Y152B")
      )
      (libsource (lib "eagle-import") (part "FERRITE_0805_0A5"))
    )
    (comp (ref "FB6")
      (value "FERRITE_0805_0A5")
      (footprint "eagle-import:RESC2012X50")
      (fields
        (field (name "CODE") "0.4 Ohm / 500 mA")
        (field (name "MANUFACTURER") "TDK")
        (field (name "MFG_PARTNO") "MMZ2012Y152B")
      )
      (libsource (lib "eagle-import") (part "FERRITE_0805_0A5"))
    )
    (comp (ref "FIDUCIAL1")
      (value "FIDUCIAL")
      (footprint "eagle-import:FIDUCIAL")
      (fields (field (name "CODE") "FIDUCIAL") (field (name "MANUFACTURER") "DNP"))
      (libsource (lib "eagle-import") (part "FIDUCIAL"))
    )
    (comp (ref "FIDUCIAL2")
      (value "FIDUCIAL")
      (footprint "eagle-import:FIDUCIAL")
      (fields (field (name "CODE") "FIDUCIAL") (field (name "MANUFACTURER") "DNP"))
      (libsource (lib "eagle-import") (part "FIDUCIAL"))
    )
    (comp (ref "FIDUCIAL3")
      (value "FIDUCIAL")
      (footprint "eagle-import:FIDUCIAL")
      (fields (field (name "CODE") "FIDUCIAL") (field (name "MANUFACTURER") "DNP"))
      (libsource (lib "eagle-import") (part "FIDUCIAL"))
    )
    (comp (ref "FIDUCIAL4")
      (value "FIDUCIAL")
      (footprint "eagle-import:FIDUCIAL")
      (fields (field (name "CODE") "FIDUCIAL") (field (name "MANUFACTURER") "DNP"))
      (libsource (lib "eagle-import") (part "FIDUCIAL"))
    )
    (comp (ref "FIDUCIAL5")
      (value "FIDUCIAL")
      (footprint "eagle-import:FIDUCIAL")
      (fields (field (name "CODE") "FIDUCIAL") (field (name "MANUFACTURER") "DNP"))
      (libsource (lib "eagle-import") (part "FIDUCIAL"))
    )
    (comp (ref "FIDUCIAL6")
      (value "FIDUCIAL")
      (footprint "eagle-import:FIDUCIAL")
      (fields (field (name "CODE") "FIDUCIAL") (field (name "MANUFACTURER") "DNP"))
      (libsource (lib "eagle-import") (part "FIDUCIAL"))
    )
    (comp (ref "H1")
      (value "SWITCH_CAP_DSA_RELEG")
      (footprint "eagle-import:SWITCH_CAP_DSA_RELEG")
      (fields
        (field (name "CODE") "Key Cap")
        (field (name "MANUFACTURER") "Pimp My Keyboard")
        (field (name "MFG_PARTNO") "DSA RELEGENDABLES")
      )
      (libsource (lib "eagle-import") (part "SWITCH_CAP_DSA_RELEG"))
    )
    (comp (ref "H2")
      (value "SWITCH_CAP_DSA_RELEG")
      (footprint "eagle-import:SWITCH_CAP_DSA_RELEG")
      (fields
        (field (name "CODE") "Key Cap")
        (field (name "MANUFACTURER") "Pimp My Keyboard")
        (field (name "MFG_PARTNO") "DSA RELEGENDABLES")
      )
      (libsource (lib "eagle-import") (part "SWITCH_CAP_DSA_RELEG"))
    )
    (comp (ref "H3")
      (value "SWITCH_CAP_DSA_RELEG")
      (footprint "eagle-import:SWITCH_CAP_DSA_RELEG")
      (fields
        (field (name "CODE") "Key Cap")
        (field (name "MANUFACTURER") "Pimp My Keyboard")
        (field (name "MFG_PARTNO") "DSA RELEGENDABLES")
      )
      (libsource (lib "eagle-import") (part "SWITCH_CAP_DSA_RELEG"))
    )
    (comp (ref "H4")
      (value "SWITCH_CAP_DSA_RELEG")
      (footprint "eagle-import:SWITCH_CAP_DSA_RELEG")
      (fields
        (field (name "CODE") "Key Cap")
        (field (name "MANUFACTURER") "Pimp My Keyboard")
        (field (name "MFG_PARTNO") "DSA RELEGENDABLES")
      )
      (libsource (lib "eagle-import") (part "SWITCH_CAP_DSA_RELEG"))
    )
    (comp (ref "H5")
      (value "SWITCH_CAP_DSA_RELEG")
      (footprint "eagle-import:SWITCH_CAP_DSA_RELEG")
      (fields
        (field (name "CODE") "Key Cap")
        (field (name "MANUFACTURER") "Pimp My Keyboard")
        (field (name "MFG_PARTNO") "DSA RELEGENDABLES")
      )
      (libsource (lib "eagle-import") (part "SWITCH_CAP_DSA_RELEG"))
    )
    (comp (ref "H6")
      (value "SWITCH_CAP_DSA_RELEG")
      (footprint "eagle-import:SWITCH_CAP_DSA_RELEG")
      (fields
        (field (name "CODE") "Key Cap")
        (field (name "MANUFACTURER") "Pimp My Keyboard")
        (field (name "MFG_PARTNO") "DSA RELEGENDABLES")
      )
      (libsource (lib "eagle-import") (part "SWITCH_CAP_DSA_RELEG"))
    )
    (comp (ref "H7")
      (value "SWITCH_CAP_DSA_RELEG")
      (footprint "eagle-import:SWITCH_CAP_DSA_RELEG")
      (fields
        (field (name "CODE") "Key Cap")
        (field (name "MANUFACTURER") "Pimp My Keyboard")
        (field (name "MFG_PARTNO") "DSA RELEGENDABLES")
      )
      (libsource (lib "eagle-import") (part "SWITCH_CAP_DSA_RELEG"))
    )
    (comp (ref "H8")
      (value "SWITCH_CAP_DSA_RELEG")
      (footprint "eagle-import:SWITCH_CAP_DSA_RELEG")
      (fields
        (field (name "CODE") "Key Cap")
        (field (name "MANUFACTURER") "Pimp My Keyboard")
        (field (name "MFG_PARTNO") "DSA RELEGENDABLES")
      )
      (libsource (lib "eagle-import") (part "SWITCH_CAP_DSA_RELEG"))
    )
    (comp (ref "L1")
      (value "L_CHOKE_EXC-34CE670U")
      (footprint "eagle-import:IND_CHOKE_EXC-34")
      (fields
        (field (name "CODE") "EXC-34CE670U")
        (field (name "MANUFACTURER") "Panasonic")
        (field (name "MFG_PARTNO") "EXC-34CE670U")
      )
      (libsource (lib "eagle-import") (part "L_CHOKE_EXC-34CE670U"))
    )
    (comp (ref "LOGO2")
      (value "ART_LOGO_TEXT_2.5MM-SILK")
      (footprint "eagle-import:ART_LOGO_TEXT_2.5MM_SILK")
      (fields (field (name "CODE") "Logo text 2.5mm silk") (field (name "MANUFACTURER") "DNP"))
      (libsource (lib "eagle-import") (part "ART_LOGO_TEXT_2.5MM-SILK"))
    )
    (comp (ref "R1")
      (value "R0805_10K_5%")
      (footprint "eagle-import:RESC2012X50")
      (fields
        (field (name "CODE") "10k")
        (field (name "MANUFACTURER") "Bourns Inc.")
        (field (name "MFG_PARTNO") "CR0805-JW-103ELF")
      )
      (libsource (lib "eagle-import") (part "R0805_10K_5%"))
    )
    (comp (ref "R2")
      (value "R0805_1K_1%")
      (footprint "eagle-import:RESC2012X50")
      (fields
        (field (name "CODE") "1k")
        (field (name "MANUFACTURER") "Yageo")
        (field (name "MFG_PARTNO") "RC0805FR-071KL")
      )
      (libsource (lib "eagle-import") (part "R0805_1K_1%"))
    )
    (comp (ref "R3")
      (value "R0805_1K_1%")
      (footprint "eagle-import:RESC2012X50")
      (fields
        (field (name "CODE") "1k")
        (field (name "MANUFACTURER") "Yageo")
        (field (name "MFG_PARTNO") "RC0805FR-071KL")
      )
      (libsource (lib "eagle-import") (part "R0805_1K_1%"))
    )
    (comp (ref "R4")
      (value "R0603_22")
      (footprint "eagle-import:RESC1608X45N")
      (fields
        (field (name "CODE") "22")
        (field (name "MANUFACTURER") "Panasonic")
        (field (name "MFG_PARTNO") "ERJ-3EKF22R0V")
      )
      (libsource (lib "eagle-import") (part "R0603_22"))
    )
    (comp (ref "R5")
      (value "R0603_22")
      (footprint "eagle-import:RESC1608X45N")
      (fields
        (field (name "CODE") "22")
        (field (name "MANUFACTURER") "Panasonic")
        (field (name "MFG_PARTNO") "ERJ-3EKF22R0V")
      )
      (libsource (lib "eagle-import") (part "R0603_22"))
    )
    (comp (ref "R6")
      (value "R0805_1M_5%")
      (footprint "eagle-import:RESC2012X50")
      (fields
        (field (name "CODE") "1M")
        (field (name "MANUFACTURER") "Yageo")
        (field (name "MFG_PARTNO") "RC0805JR-071ML")
      )
      (libsource (lib "eagle-import") (part "R0805_1M_5%"))
    )
    (comp (ref "R7")
      (value "R0805_10K_5%")
      (footprint "eagle-import:RESC2012X50")
      (fields
        (field (name "CODE") "10k")
        (field (name "MANUFACTURER") "Bourns Inc.")
        (field (name "MFG_PARTNO") "CR0805-JW-103ELF")
      )
      (libsource (lib "eagle-import") (part "R0805_10K_5%"))
    )
    (comp (ref "R8")
      (value "R0805_200_1%")
      (footprint "eagle-import:RESC2012X50")
      (fields
        (field (name "CODE") "200")
        (field (name "MANUFACTURER") "Yageo")
        (field (name "MFG_PARTNO") "RC0805FR-07200RL")
      )
      (libsource (lib "eagle-import") (part "R0805_200_1%"))
    )
    (comp (ref "R9")
      (value "R0805_200_1%")
      (footprint "eagle-import:RESC2012X50")
      (fields
        (field (name "CODE") "200")
        (field (name "MANUFACTURER") "Yageo")
        (field (name "MFG_PARTNO") "RC0805FR-07200RL")
      )
      (libsource (lib "eagle-import") (part "R0805_200_1%"))
    )
    (comp (ref "R10")
      (value "R0805_200_1%")
      (footprint "eagle-import:RESC2012X50")
      (fields
        (field (name "CODE") "200")
        (field (name "MANUFACTURER") "Yageo")
        (field (name "MFG_PARTNO") "RC0805FR-07200RL")
      )
      (libsource (lib "eagle-import") (part "R0805_200_1%"))
    )
    (comp (ref "R11")
      (value "R0805_200_1%")
      (footprint "eagle-import:RESC2012X50")
      (fields
        (field (name "CODE") "200")
        (field (name "MANUFACTURER") "Yageo")
        (field (name "MFG_PARTNO") "RC0805FR-07200RL")
      )
      (libsource (lib "eagle-import") (part "R0805_200_1%"))
    )
    (comp (ref "R12")
      (value "R0805_200_1%")
      (footprint "eagle-import:RESC2012X50")
      (fields
        (field (name "CODE") "200")
        (field (name "MANUFACTURER") "Yageo")
        (field (name "MFG_PARTNO") "RC0805FR-07200RL")
      )
      (libsource (lib "eagle-import") (part "R0805_200_1%"))
    )
    (comp (ref "R13")
      (value "R0805_1K_1%")
      (footprint "eagle-import:RESC2012X50")
      (fields
        (field (name "CODE") "1k")
        (field (name "MANUFACTURER") "Yageo")
        (field (name "MFG_PARTNO") "RC0805FR-071KL")
      )
      (libsource (lib "eagle-import") (part "R0805_1K_1%"))
    )
    (comp (ref "R14")
      (value "R0805_200_1%")
      (footprint "eagle-import:RESC2012X50")
      (fields
        (field (name "CODE") "200")
        (field (name "MANUFACTURER") "Yageo")
        (field (name "MFG_PARTNO") "RC0805FR-07200RL")
      )
      (libsource (lib "eagle-import") (part "R0805_200_1%"))
    )
    (comp (ref "R15")
      (value "R0805_200_1%")
      (footprint "eagle-import:RESC2012X50")
      (fields
        (field (name "CODE") "200")
        (field (name "MANUFACTURER") "Yageo")
        (field (name "MFG_PARTNO") "RC0805FR-07200RL")
      )
      (libsource (lib "eagle-import") (part "R0805_200_1%"))
    )
    (comp (ref "R16")
      (value "R0402_DNP")
      (footprint "eagle-import:RESC1005X35N")
      (fields (field (name "CODE") "DNP") (field (name "MANUFACTURER") "DNP"))
      (libsource (lib "eagle-import") (part "R0402_DNP"))
    )
    (comp (ref "R17")
      (value "R0805_3K3_1%")
      (footprint "eagle-import:RESC2012X50")
      (fields
        (field (name "CODE") "3k3")
        (field (name "MANUFACTURER") "Yageo")
        (field (name "MFG_PARTNO") "RC0805FR-073K3L")
      )
      (libsource (lib "eagle-import") (part "R0805_3K3_1%"))
    )
    (comp (ref "R18")
      (value "R0805_1K_1%")
      (footprint "eagle-import:RESC2012X50")
      (fields
        (field (name "CODE") "1k")
        (field (name "MANUFACTURER") "Yageo")
        (field (name "MFG_PARTNO") "RC0805FR-071KL")
      )
      (libsource (lib "eagle-import") (part "R0805_1K_1%"))
    )
    (comp (ref "R19")
      (value "R0805_200_1%")
      (footprint "eagle-import:RESC2012X50")
      (fields
        (field (name "CODE") "200")
        (field (name "MANUFACTURER") "Yageo")
        (field (name "MFG_PARTNO") "RC0805FR-07200RL")
      )
      (libsource (lib "eagle-import") (part "R0805_200_1%"))
    )
    (comp (ref "R20")
      (value "R0805_3K3_1%")
      (footprint "eagle-import:RESC2012X50")
      (fields
        (field (name "CODE") "3k3")
        (field (name "MANUFACTURER") "Yageo")
        (field (name "MFG_PARTNO") "RC0805FR-073K3L")
      )
      (libsource (lib "eagle-import") (part "R0805_3K3_1%"))
    )
    (comp (ref "R21")
      (value "R0805_200_1%")
      (footprint "eagle-import:RESC2012X50")
      (fields
        (field (name "CODE") "200")
        (field (name "MANUFACTURER") "Yageo")
        (field (name "MFG_PARTNO") "RC0805FR-07200RL")
      )
      (libsource (lib "eagle-import") (part "R0805_200_1%"))
    )
    (comp (ref "R22")
      (value "R0805_200_1%")
      (footprint "eagle-import:RESC2012X50")
      (fields
        (field (name "CODE") "200")
        (field (name "MANUFACTURER") "Yageo")
        (field (name "MFG_PARTNO") "RC0805FR-07200RL")
      )
      (libsource (lib "eagle-import") (part "R0805_200_1%"))
    )
    (comp (ref "R23")
      (value "R0805_1K_1%")
      (footprint "eagle-import:RESC2012X50")
      (fields
        (field (name "CODE") "1k")
        (field (name "MANUFACTURER") "Yageo")
        (field (name "MFG_PARTNO") "RC0805FR-071KL")
      )
      (libsource (lib "eagle-import") (part "R0805_1K_1%"))
    )
    (comp (ref "R24")
      (value "R0603_0")
      (footprint "eagle-import:RESC1608X45N")
      (fields
        (field (name "CODE") "0")
        (field (name "MANUFACTURER") "Panasonic")
        (field (name "MFG_PARTNO") "ERJ-3GEY0R00V")
      )
      (libsource (lib "eagle-import") (part "R0603_0"))
    )
    (comp (ref "R25")
      (value "R0805_1K_1%")
      (footprint "eagle-import:RESC2012X50")
      (fields
        (field (name "CODE") "1k")
        (field (name "MANUFACTURER") "Yageo")
        (field (name "MFG_PARTNO") "RC0805FR-071KL")
      )
      (libsource (lib "eagle-import") (part "R0805_1K_1%"))
    )
    (comp (ref "R26")
      (value "R0805_1K_1%")
      (footprint "eagle-import:RESC2012X50")
      (fields
        (field (name "CODE") "1k")
        (field (name "MANUFACTURER") "Yageo")
        (field (name "MFG_PARTNO") "RC0805FR-071KL")
      )
      (libsource (lib "eagle-import") (part "R0805_1K_1%"))
    )
    (comp (ref "R27")
      (value "R0805_1K_1%")
      (footprint "eagle-import:RESC2012X50")
      (fields
        (field (name "CODE") "1k")
        (field (name "MANUFACTURER") "Yageo")
        (field (name "MFG_PARTNO") "RC0805FR-071KL")
      )
      (libsource (lib "eagle-import") (part "R0805_1K_1%"))
    )
    (comp (ref "R28")
      (value "R0805_1K_1%")
      (footprint "eagle-import:RESC2012X50")
      (fields
        (field (name "CODE") "1k")
        (field (name "MANUFACTURER") "Yageo")
        (field (name "MFG_PARTNO") "RC0805FR-071KL")
      )
      (libsource (lib "eagle-import") (part "R0805_1K_1%"))
    )
    (comp (ref "R29")
      (value "R0805_1K_1%")
      (footprint "eagle-import:RESC2012X50")
      (fields
        (field (name "CODE") "1k")
        (field (name "MANUFACTURER") "Yageo")
        (field (name "MFG_PARTNO") "RC0805FR-071KL")
      )
      (libsource (lib "eagle-import") (part "R0805_1K_1%"))
    )
    (comp (ref "R30")
      (value "R0805_1K_1%")
      (footprint "eagle-import:RESC2012X50")
      (fields
        (field (name "CODE") "1k")
        (field (name "MANUFACTURER") "Yageo")
        (field (name "MFG_PARTNO") "RC0805FR-071KL")
      )
      (libsource (lib "eagle-import") (part "R0805_1K_1%"))
    )
    (comp (ref "R31")
      (value "R0805_200_1%")
      (footprint "eagle-import:RESC2012X50")
      (fields
        (field (name "CODE") "200")
        (field (name "MANUFACTURER") "Yageo")
        (field (name "MFG_PARTNO") "RC0805FR-07200RL")
      )
      (libsource (lib "eagle-import") (part "R0805_200_1%"))
    )
    (comp (ref "R32")
      (value "R0603_0")
      (footprint "eagle-import:RESC1608X45N")
      (fields
        (field (name "CODE") "0")
        (field (name "MANUFACTURER") "Panasonic")
        (field (name "MFG_PARTNO") "ERJ-3GEY0R00V")
      )
      (libsource (lib "eagle-import") (part "R0603_0"))
    )
    (comp (ref "R33")
      (value "R0603_0")
      (footprint "eagle-import:RESC1608X45N")
      (fields
        (field (name "CODE") "0")
        (field (name "MANUFACTURER") "Panasonic")
        (field (name "MFG_PARTNO") "ERJ-3GEY0R00V")
      )
      (libsource (lib "eagle-import") (part "R0603_0"))
    )
    (comp (ref "S1")
      (value "SWITCH_BUTTON_MX1A-C1NW")
      (footprint "eagle-import:SWITCH_BUTTON_CHERRY_MX")
      (fields
        (field (name "CODE") "MX1A-C1NW")
        (field (name "MANUFACTURER") "Cherry")
        (field (name "MFG_PARTNO") "MX1A-C1NW")
      )
      (libsource (lib "eagle-import") (part "SWITCH_BUTTON_MX1A-C1NW"))
    )
    (comp (ref "S3")
      (value "SWITCH_BUTTON_MX1A-C1NW")
      (footprint "eagle-import:SWITCH_BUTTON_CHERRY_MX")
      (fields
        (field (name "CODE") "MX1A-C1NW")
        (field (name "MANUFACTURER") "Cherry")
        (field (name "MFG_PARTNO") "MX1A-C1NW")
      )
      (libsource (lib "eagle-import") (part "SWITCH_BUTTON_MX1A-C1NW"))
    )
    (comp (ref "S4")
      (value "SWITCH_BUTTON_MX1A-C1NW")
      (footprint "eagle-import:SWITCH_BUTTON_CHERRY_MX")
      (fields
        (field (name "CODE") "MX1A-C1NW")
        (field (name "MANUFACTURER") "Cherry")
        (field (name "MFG_PARTNO") "MX1A-C1NW")
      )
      (libsource (lib "eagle-import") (part "SWITCH_BUTTON_MX1A-C1NW"))
    )
    (comp (ref "S5")
      (value "SWITCH_BUTTON_MX1A-C1NW")
      (footprint "eagle-import:SWITCH_BUTTON_CHERRY_MX")
      (fields
        (field (name "CODE") "MX1A-C1NW")
        (field (name "MANUFACTURER") "Cherry")
        (field (name "MFG_PARTNO") "MX1A-C1NW")
      )
      (libsource (lib "eagle-import") (part "SWITCH_BUTTON_MX1A-C1NW"))
    )
    (comp (ref "S6")
      (value "SWITCH_BUTTON_MX1A-C1NW")
      (footprint "eagle-import:SWITCH_BUTTON_CHERRY_MX")
      (fields
        (field (name "CODE") "MX1A-C1NW")
        (field (name "MANUFACTURER") "Cherry")
        (field (name "MFG_PARTNO") "MX1A-C1NW")
      )
      (libsource (lib "eagle-import") (part "SWITCH_BUTTON_MX1A-C1NW"))
    )
    (comp (ref "S7")
      (value "SWITCH_BUTTON_MX1A-C1NW")
      (footprint "eagle-import:SWITCH_BUTTON_CHERRY_MX")
      (fields
        (field (name "CODE") "MX1A-C1NW")
        (field (name "MANUFACTURER") "Cherry")
        (field (name "MFG_PARTNO") "MX1A-C1NW")
      )
      (libsource (lib "eagle-import") (part "SWITCH_BUTTON_MX1A-C1NW"))
    )
    (comp (ref "S8")
      (value "SWITCH_BUTTON_MX1A-C1NW")
      (footprint "eagle-import:SWITCH_BUTTON_CHERRY_MX")
      (fields
        (field (name "CODE") "MX1A-C1NW")
        (field (name "MANUFACTURER") "Cherry")
        (field (name "MFG_PARTNO") "MX1A-C1NW")
      )
      (libsource (lib "eagle-import") (part "SWITCH_BUTTON_MX1A-C1NW"))
    )
    (comp (ref "S9")
      (value "SWITCH_BUTTON_MX1A-C1NW")
      (footprint "eagle-import:SWITCH_BUTTON_CHERRY_MX")
      (fields
        (field (name "CODE") "MX1A-C1NW")
        (field (name "MANUFACTURER") "Cherry")
        (field (name "MFG_PARTNO") "MX1A-C1NW")
      )
      (libsource (lib "eagle-import") (part "SWITCH_BUTTON_MX1A-C1NW"))
    )
    (comp (ref "S10")
      (value "SWITCH_MOM_SPST_FSM4JSMA")
      (footprint "eagle-import:SWITCH_BUTTON_TE_FSM4JSMA")
      (fields
        (field (name "CODE") "Button")
        (field (name "MANUFACTURER") "TE Connectivity")
        (field (name "MFG_PARTNO") "FSM4JSMA")
      )
      (libsource (lib "eagle-import") (part "SWITCH_MOM_SPST_FSM4JSMA"))
    )
    (comp (ref "TP1")
      (value "PAD_TEST_POINT-2.5/0.7_A")
      (footprint "eagle-import:TEST_POINT_2.5MM_0.7HOLE_1SIDE")
      (fields
        (field (name "INFO") "Edit \"INFO\" attribute")
        (field (name "MANUFACTURER") "Do not populate")
        (field (name "MFG_PARTNO") "DNP")
        (field (name "INFO_1") "CLK 3V3")
      )
      (libsource (lib "eagle-import") (part "PAD_TEST_POINT-2.5/0.7_A"))
    )
    (comp (ref "TP2")
      (value "PAD_TEST_POINT-2.5/0.7_A")
      (footprint "eagle-import:TEST_POINT_2.5MM_0.7HOLE_1SIDE")
      (fields
        (field (name "INFO") "Edit \"INFO\" attribute")
        (field (name "MANUFACTURER") "Do not populate")
        (field (name "MFG_PARTNO") "DNP")
        (field (name "INFO_1") "CLK 5 V")
      )
      (libsource (lib "eagle-import") (part "PAD_TEST_POINT-2.5/0.7_A"))
    )
    (comp (ref "TP3")
      (value "PAD_TEST_POINT-2.5/0.7_A")
      (footprint "eagle-import:TEST_POINT_2.5MM_0.7HOLE_1SIDE")
      (fields
        (field (name "MANUFACTURER") "Do not populate")
        (field (name "MFG_PARTNO") "DNP")
        (field (name "INFO") "3V3")
      )
      (libsource (lib "eagle-import") (part "PAD_TEST_POINT-2.5/0.7_A"))
    )
    (comp (ref "TP5")
      (value "PAD_TEST_POINT-2.5/0.7_A")
      (footprint "eagle-import:TEST_POINT_2.5MM_0.7HOLE_1SIDE")
      (fields
        (field (name "INFO") "Edit \"INFO\" attribute")
        (field (name "MANUFACTURER") "Do not populate")
        (field (name "MFG_PARTNO") "DNP")
        (field (name "INFO_1") "!RESET")
      )
      (libsource (lib "eagle-import") (part "PAD_TEST_POINT-2.5/0.7_A"))
    )
    (comp (ref "TP7")
      (value "PAD_TEST_POINT-2.5/0.7_A")
      (footprint "eagle-import:TEST_POINT_2.5MM_0.7HOLE_1SIDE")
      (fields
        (field (name "MANUFACTURER") "Do not populate")
        (field (name "MFG_PARTNO") "DNP")
        (field (name "INFO") "5 V")
      )
      (libsource (lib "eagle-import") (part "PAD_TEST_POINT-2.5/0.7_A"))
    )
    (comp (ref "TP15")
      (value "PAD_TEST_POINT-2.5/0.7_A")
      (footprint "eagle-import:TEST_POINT_2.5MM_0.7HOLE_1SIDE")
      (fields
        (field (name "INFO") "Edit \"INFO\" attribute")
        (field (name "MANUFACTURER") "Do not populate")
        (field (name "MFG_PARTNO") "DNP")
        (field (name "INFO_1") "CLK_5V")
      )
      (libsource (lib "eagle-import") (part "PAD_TEST_POINT-2.5/0.7_A"))
    )
    (comp (ref "TP16")
      (value "PAD_TEST_POINT-2.5/0.7_A")
      (footprint "eagle-import:TEST_POINT_2.5MM_0.7HOLE_1SIDE")
      (fields
        (field (name "MANUFACTURER") "Do not populate")
        (field (name "MFG_PARTNO") "DNP")
        (field (name "INFO") "MISO")
      )
      (libsource (lib "eagle-import") (part "PAD_TEST_POINT-2.5/0.7_A"))
    )
    (comp (ref "TP17")
      (value "PAD_TEST_POINT-2.5/0.7_A")
      (footprint "eagle-import:TEST_POINT_2.5MM_0.7HOLE_1SIDE")
      (fields
        (field (name "MANUFACTURER") "Do not populate")
        (field (name "MFG_PARTNO") "DNP")
        (field (name "INFO") "MOSI_5V")
      )
      (libsource (lib "eagle-import") (part "PAD_TEST_POINT-2.5/0.7_A"))
    )
    (comp (ref "U1")
      (value "IC_MCU_ATMEGA32U4-AU")
      (footprint "eagle-import:QFP80P1000X1000X120-44R_N")
      (fields
        (field (name "CODE") "ATMEGA32U4")
        (field (name "MANUFACTURER") "Microchip")
        (field (name "MFG_PARTNO") "ATMEGA32U4-AU")
      )
      (libsource (lib "eagle-import") (part "IC_MCU_ATMEGA32U4-AU"))
    )
    (comp (ref "U2")
      (value "IC_MEM_FLASH_AT45DB321E")
      (footprint "eagle-import:SOP127P800X175-8")
      (fields
        (field (name "CODE") "AT45DB321E-SHF-T ")
        (field (name "MANUFACTURER") "Adesto Technologies")
        (field (name "MFG_PARTNO") "AT45DB321E-SHF-T ")
      )
      (libsource (lib "eagle-import") (part "IC_MEM_FLASH_AT45DB321E"))
    )
    (comp (ref "U3")
      (value "IC_REG_3V3_1A_NCP1117LPST33T3G")
      (footprint "eagle-import:SOT223")
      (fields
        (field (name "CODE") "1117-3v3")
        (field (name "MANUFACTURER") "ON Semiconductor")
        (field (name "MFG_PARTNO") "NCP1117LPST33T3G")
      )
      (libsource (lib "eagle-import") (part "IC_REG_3V3_1A_NCP1117LPST33T3G"))
    )
    (comp (ref "U4")
      (value "IC_LEVEL_SHIFTER_SN74LVC2T45")
      (footprint "eagle-import:SOP65P400X130-8")
      (fields
        (field (name "CODE") "SN74LVC2T45DCTT")
        (field (name "MANUFACTURER") "Texas Instruments")
        (field (name "MFG_PARTNO") "SN74LVC2T45DCTT")
      )
      (libsource (lib "eagle-import") (part "IC_LEVEL_SHIFTER_SN74LVC2T45"))
    )
    (comp (ref "U5")
      (value "IC_LEVEL_SHIFTER_SN74LVC2T45")
      (footprint "eagle-import:SOP65P400X130-8")
      (fields
        (field (name "CODE") "SN74LVC2T45DCTT")
        (field (name "MANUFACTURER") "Texas Instruments")
        (field (name "MFG_PARTNO") "SN74LVC2T45DCTT")
      )
      (libsource (lib "eagle-import") (part "IC_LEVEL_SHIFTER_SN74LVC2T45"))
    )
    (comp (ref "U6")
      (value "IC_LEVEL_SHIFTER_SN74LVC2T45")
      (footprint "eagle-import:SOP65P400X130-8")
      (fields
        (field (name "CODE") "SN74LVC2T45DCTT")
        (field (name "MANUFACTURER") "Texas Instruments")
        (field (name "MFG_PARTNO") "SN74LVC2T45DCTT")
      )
      (libsource (lib "eagle-import") (part "IC_LEVEL_SHIFTER_SN74LVC2T45"))
    )
    (comp (ref "X1")
      (value "CON_USB_MICROB_UJ2-MIBH-4-SMT-TR-MAN")
      (footprint "eagle-import:CON_USB_MICROB_UJ2-MIBH-4-SMT-TR_MAN")
      (fields
        (field (name "CODE") "UJ2-MIBH-4-SMT-TR")
        (field (name "MANUFACTURER") "CUI")
        (field (name "MFG_PARTNO") "UJ2-MIBH-4-SMT-TR")
      )
      (libsource (lib "eagle-import") (part "CON_USB_MICROB_UJ2-MIBH-4-SMT-TR-MAN"))
    )
    (comp (ref "X2")
      (value "CON_PROG_AVR_ISP-OFFSET_1X06")
      (footprint "eagle-import:CON_PINHD_1X06_TH_OFFSET")
      (fields (field (name "CODE") "1x06 offset") (field (name "MANUFACTURER") "DNP"))
      (libsource (lib "eagle-import") (part "CON_PROG_AVR_ISP-OFFSET_1X06"))
    )
    (comp (ref "X3")
      (value "CON_1X04_TH_OFFSET_PADS-SILK")
      (footprint "eagle-import:1X04_TH_OFFSET")
      (fields (field (name "CODE") "1X04") (field (name "MANUFACTURER") "DNP"))
      (libsource (lib "eagle-import") (part "CON_1X04_TH_OFFSET_PADS-SILK"))
    )
    (comp (ref "X4")
      (value "HOL_3.2/6.0_NP")
      (footprint "eagle-import:MTG_NP_M3_320X600")
      (fields (field (name "CODE") "NP 3.2 mm") (field (name "MANUFACTURER") "DNP"))
      (libsource (lib "eagle-import") (part "HOL_3.2/6.0_NP"))
    )
    (comp (ref "X5")
      (value "HOL_3.2/6.0_NP")
      (footprint "eagle-import:MTG_NP_M3_320X600")
      (fields (field (name "CODE") "NP 3.2 mm") (field (name "MANUFACTURER") "DNP"))
      (libsource (lib "eagle-import") (part "HOL_3.2/6.0_NP"))
    )
    (comp (ref "X6")
      (value "HOL_3.2/6.0_NP")
      (footprint "eagle-import:MTG_NP_M3_320X600")
      (fields (field (name "CODE") "NP 3.2 mm") (field (name "MANUFACTURER") "DNP"))
      (libsource (lib "eagle-import") (part "HOL_3.2/6.0_NP"))
    )
    (comp (ref "X9")
      (value "HOL_3.2/6.0_NP")
      (footprint "eagle-import:MTG_NP_M3_320X600")
      (fields (field (name "CODE") "NP 3.2 mm") (field (name "MANUFACTURER") "DNP"))
      (libsource (lib "eagle-import") (part "HOL_3.2/6.0_NP"))
    )
    (comp (ref "X10")
      (value "HOL_3.2/6.0_NP")
      (footprint "eagle-import:MTG_NP_M3_320X600")
      (fields (field (name "CODE") "NP 3.2 mm") (field (name "MANUFACTURER") "DNP"))
      (libsource (lib "eagle-import") (part "HOL_3.2/6.0_NP"))
    )
    (comp (ref "X11")
      (value "CON_MICROSD_MOLEX_5033981892-M")
      (footprint "eagle-import:CON_MICROSD_MOLEX_5033981892_M")
      (fields
        (field (name "CODE") "503398-1892")
        (field (name "MANUFACTURER") "Molex")
        (field (name "MFG_PARTNO") "5033981892")
      )
      (libsource (lib "eagle-import") (part "CON_MICROSD_MOLEX_5033981892-M"))
    )
    (comp (ref "X12")
      (value "HOL_3.2/6.0_NP")
      (footprint "eagle-import:MTG_NP_M3_320X600")
      (fields (field (name "CODE") "NP 3.2 mm") (field (name "MANUFACTURER") "DNP"))
      (libsource (lib "eagle-import") (part "HOL_3.2/6.0_NP"))
    )
    (comp (ref "X13")
      (value "PAD_TEST_GROUND_HOOK")
      (footprint "eagle-import:PAD_GND_HOOK_M")
      (fields (field (name "MANUFACTURER") "Do not populate") (field (name "MFG_PARTNO") "DNP"))
      (libsource (lib "eagle-import") (part "PAD_TEST_GROUND_HOOK"))
    )
    (comp (ref "X14")
      (value "CON_CLAMP_PTSM_1X04_H_SMD")
      (footprint "eagle-import:CON_PHOENIX_CONTACT_1702474")
      (fields
        (field (name "CODE") "1702474")
        (field (name "MANUFACTURER") "Phoenix Contact")
        (field (name "MFG_PARTNO") "1702474")
      )
      (libsource (lib "eagle-import") (part "CON_CLAMP_PTSM_1X04_H_SMD"))
    )
    (comp (ref "X15")
      (value "CON_CLAMP_PTSM_1X08_H_SMD")
      (footprint "eagle-import:CON_PHOENIX_CONTACT_1771088")
      (fields
        (field (name "CODE") "1771088")
        (field (name "MANUFACTURER") "Phoenix Contact")
        (field (name "MFG_PARTNO") "1771088")
      )
      (libsource (lib "eagle-import") (part "CON_CLAMP_PTSM_1X08_H_SMD"))
    )
    (comp (ref "X17")
      (value "HOL_3.2/6.0_NP")
      (footprint "eagle-import:MTG_NP_M3_320X600")
      (fields (field (name "CODE") "NP 3.2 mm") (field (name "MANUFACTURER") "DNP"))
      (libsource (lib "eagle-import") (part "HOL_3.2/6.0_NP"))
    )
    (comp (ref "X18")
      (value "HOL_3.2/6.0_NP")
      (footprint "eagle-import:MTG_NP_M3_320X600")
      (fields (field (name "CODE") "NP 3.2 mm") (field (name "MANUFACTURER") "DNP"))
      (libsource (lib "eagle-import") (part "HOL_3.2/6.0_NP"))
    )
    (comp (ref "Y1")
      (value "OSC_CRYSTAL_16M_ABLS-16.000MHZ-B4-T-HC49")
      (footprint "eagle-import:OSC_CRYSTAL_HC49_US")
      (fields
        (field (name "CODE") "16M")
        (field (name "MANUFACTURER") "Abracon LLC")
        (field (name "MFG_PARTNO") "ABLS-16.000MHZ-B4-T")
      )
      (libsource (lib "eagle-import") (part "OSC_CRYSTAL_16M_ABLS-16.000MHZ-B4-T-HC49"))
    )
  )
  (nets
    (net (code "1") (name "+3V3") (class "Default")
      (node (ref "C19") (pin "P$2") (pinfunction "2_P$2") (pintype "passive"))
      (node (ref "C20") (pin "P$2") (pinfunction "2_P$2") (pintype "passive"))
      (node (ref "C28") (pin "P$1") (pinfunction "1_P$1") (pintype "passive"))
      (node (ref "C29") (pin "P$1") (pinfunction "1_P$1") (pintype "passive"))
      (node (ref "C31") (pin "P$1") (pinfunction "1_P$1") (pintype "passive"))
      (node (ref "C34") (pin "P$1") (pinfunction "1_P$1") (pintype "passive"))
      (node (ref "C44") (pin "P$1") (pinfunction "1_P$1") (pintype "passive"))
      (node (ref "C46") (pin "P$2") (pinfunction "2_P$2") (pintype "passive"))
      (node (ref "C9") (pin "P$2") (pinfunction "2_P$2") (pintype "passive"))
      (node (ref "R32") (pin "P$2") (pinfunction "2_P$2") (pintype "passive"))
      (node (ref "R33") (pin "P$2") (pinfunction "2_P$2") (pintype "passive"))
      (node (ref "TP3") (pin "P$1") (pinfunction "P$1_P$1") (pintype "bidirectional"))
      (node (ref "U2") (pin "6") (pinfunction "V+_6") (pintype "bidirectional"))
      (node (ref "U3") (pin "2") (pinfunction "VO_2") (pintype "passive"))
      (node (ref "U3") (pin "4") (pinfunction "VO_4") (pintype "passive"))
      (node (ref "U4") (pin "8") (pinfunction "VB_8") (pintype "power_in"))
      (node (ref "U5") (pin "8") (pinfunction "VB_8") (pintype "power_in"))
      (node (ref "U6") (pin "8") (pinfunction "VB_8") (pintype "power_in"))
      (node (ref "X11") (pin "4") (pinfunction "VDD_4") (pintype "bidirectional"))
    )
    (net (code "2") (name "+5V") (class "Default")
      (node (ref "C12") (pin "P$1") (pinfunction "1_P$1") (pintype "passive"))
      (node (ref "C21") (pin "P$2") (pinfunction "2_P$2") (pintype "passive"))
      (node (ref "C3") (pin "P$1") (pinfunction "1_P$1") (pintype "passive"))
      (node (ref "C30") (pin "P$2") (pinfunction "2_P$2") (pintype "passive"))
      (node (ref "C32") (pin "P$1") (pinfunction "1_P$1") (pintype "passive"))
      (node (ref "C33") (pin "P$2") (pinfunction "2_P$2") (pintype "passive"))
      (node (ref "C4") (pin "P$1") (pinfunction "1_P$1") (pintype "passive"))
      (node (ref "C48") (pin "P$1") (pinfunction "1_P$1") (pintype "passive"))
      (node (ref "C5") (pin "P$1") (pinfunction "1_P$1") (pintype "passive"))
      (node (ref "C6") (pin "P$1") (pinfunction "1_P$1") (pintype "passive"))
      (node (ref "D1") (pin "5") (pinfunction "V+_5") (pintype "bidirectional"))
      (node (ref "D2") (pin "C") (pinfunction "K_C") (pintype "passive"))
      (node (ref "FB1") (pin "P$2") (pinfunction "2_P$2") (pintype "passive"))
      (node (ref "FB3") (pin "P$1") (pinfunction "1_P$1") (pintype "passive"))
      (node (ref "FB6") (pin "P$2") (pinfunction "2_P$2") (pintype "passive"))
      (node (ref "R1") (pin "P$2") (pinfunction "2_P$2") (pintype "passive"))
      (node (ref "R16") (pin "P$2") (pinfunction "2_P$2") (pintype "passive"))
      (node (ref "R17") (pin "P$2") (pinfunction "2_P$2") (pintype "passive"))
      (node (ref "R20") (pin "P$2") (pinfunction "2_P$2") (pintype "passive"))
      (node (ref "R23") (pin "P$2") (pinfunction "2_P$2") (pintype "passive"))
      (node (ref "TP7") (pin "P$1") (pinfunction "P$1_P$1") (pintype "bidirectional"))
      (node (ref "U1") (pin "14") (pinfunction "VCC_14") (pintype "bidirectional"))
      (node (ref "U1") (pin "2") (pinfunction "UVCC_2") (pintype "bidirectional"))
      (node (ref "U1") (pin "34") (pinfunction "VCC1_34") (pintype "bidirectional"))
      (node (ref "U3") (pin "3") (pinfunction "VI_3") (pintype "input"))
      (node (ref "U4") (pin "1") (pinfunction "VA_1") (pintype "power_in"))
      (node (ref "U4") (pin "5") (pinfunction "DIR_5") (pintype "input"))
      (node (ref "U5") (pin "1") (pinfunction "VA_1") (pintype "power_in"))
      (node (ref "U6") (pin "1") (pinfunction "VA_1") (pintype "power_in"))
      (node (ref "U6") (pin "5") (pinfunction "DIR_5") (pintype "input"))
    )
    (net (code "3") (name "/~{CS}_FLASH_3V3") (class "Default")
      (node (ref "U2") (pin "4") (pinfunction "~{CS}_4") (pintype "bidirectional"))
      (node (ref "U6") (pin "6") (pinfunction "B2_6") (pintype "bidirectional"))
    )
    (net (code "4") (name "/~{CS}_FLASH_5V") (class "Default")
      (node (ref "U1") (pin "31") (pinfunction "PC6(OC3A/~{OC4A})_31") (pintype "bidirectional"))
      (node (ref "U6") (pin "3") (pinfunction "A2_3") (pintype "bidirectional"))
    )
    (net (code "5") (name "/~{CS}_SD_3V3") (class "Default")
      (node (ref "U6") (pin "7") (pinfunction "B1_7") (pintype "bidirectional"))
      (node (ref "X11") (pin "2") (pinfunction "CD/DAT3_2") (pintype "bidirectional"))
    )
    (net (code "6") (name "/~{CS}_SD_5V") (class "Default")
      (node (ref "U1") (pin "25") (pinfunction "PD4(ICP1/ADC8)_25") (pintype "bidirectional"))
      (node (ref "U6") (pin "2") (pinfunction "A1_2") (pintype "bidirectional"))
    )
    (net (code "7") (name "/~{RESET}") (class "Default")
      (node (ref "R1") (pin "P$1") (pinfunction "1_P$1") (pintype "passive"))
      (node (ref "S10") (pin "1") (pinfunction "P$1_1") (pintype "bidirectional"))
      (node (ref "TP5") (pin "P$1") (pinfunction "P$1_P$1") (pintype "bidirectional"))
      (node (ref "U1") (pin "13") (pinfunction "~{RESET}_13") (pintype "bidirectional"))
      (node (ref "X2") (pin "5") (pinfunction "RST_5") (pintype "output"))
      (node (ref "X3") (pin "1") (pinfunction "1_1") (pintype "passive"))
    )
    (net (code "8") (name "/~{RESET}_3V3") (class "Default")
      (node (ref "R32") (pin "P$1") (pinfunction "1_P$1") (pintype "passive"))
      (node (ref "U2") (pin "3") (pinfunction "~{RESET}_3") (pintype "bidirectional"))
    )
    (net (code "9") (name "AD0") (class "Default")
      (node (ref "C22") (pin "P$1") (pinfunction "1_P$1") (pintype "passive"))
      (node (ref "R25") (pin "P$2") (pinfunction "2_P$2") (pintype "passive"))
      (node (ref "U1") (pin "36") (pinfunction "PF7(ADC7(TDI)_36") (pintype "bidirectional"))
    )
    (net (code "10") (name "AD1") (class "Default")
      (node (ref "C23") (pin "P$1") (pinfunction "1_P$1") (pintype "passive"))
      (node (ref "R26") (pin "P$2") (pinfunction "2_P$2") (pintype "passive"))
      (node (ref "U1") (pin "37") (pinfunction "PF6(ADC6/TDO)_37") (pintype "bidirectional"))
    )
    (net (code "11") (name "AD4") (class "Default")
      (node (ref "C24") (pin "P$1") (pinfunction "1_P$1") (pintype "passive"))
      (node (ref "R27") (pin "P$2") (pinfunction "2_P$2") (pintype "passive"))
      (node (ref "U1") (pin "38") (pinfunction "PF5(ADC5/TMS)_38") (pintype "bidirectional"))
    )
    (net (code "12") (name "AD5") (class "Default")
      (node (ref "C25") (pin "P$1") (pinfunction "1_P$1") (pintype "passive"))
      (node (ref "R28") (pin "P$2") (pinfunction "2_P$2") (pintype "passive"))
      (node (ref "U1") (pin "39") (pinfunction "PF4(ADC4/TCK)_39") (pintype "bidirectional"))
    )
    (net (code "13") (name "AD6") (class "Default")
      (node (ref "C26") (pin "P$1") (pinfunction "1_P$1") (pintype "passive"))
      (node (ref "R29") (pin "P$2") (pinfunction "2_P$2") (pintype "passive"))
      (node (ref "U1") (pin "40") (pinfunction "PF1(ADC1)_40") (pintype "bidirectional"))
    )
    (net (code "14") (name "AD7") (class "Default")
      (node (ref "C27") (pin "P$1") (pinfunction "1_P$1") (pintype "passive"))
      (node (ref "R30") (pin "P$2") (pinfunction "2_P$2") (pintype "passive"))
      (node (ref "U1") (pin "41") (pinfunction "PF0(ADC0)_41") (pintype "bidirectional"))
    )
    (net (code "15") (name "BUTTON1") (class "Default")
      (node (ref "C10") (pin "P$1") (pinfunction "1_P$1") (pintype "passive"))
      (node (ref "R8") (pin "P$2") (pinfunction "2_P$2") (pintype "passive"))
      (node (ref "U1") (pin "26") (pinfunction "PD6(T1/ADC9/~{OC4D})_26") (pintype "bidirectional"))
    )
    (net (code "16") (name "BUTTON2") (class "Default")
      (node (ref "C11") (pin "P$1") (pinfunction "1_P$1") (pintype "passive"))
      (node (ref "R9") (pin "P$2") (pinfunction "2_P$2") (pintype "passive"))
      (node (ref "U1") (pin "27") (pinfunction "PD7(OC4D/ADC10/T0)_27") (pintype "bidirectional"))
    )
    (net (code "17") (name "BUTTON3") (class "Default")
      (node (ref "C13") (pin "P$1") (pinfunction "1_P$1") (pintype "passive"))
      (node (ref "R10") (pin "P$2") (pinfunction "2_P$2") (pintype "passive"))
      (node (ref "U1") (pin "28") (pinfunction "PB4(ADC11)_28") (pintype "bidirectional"))
    )
    (net (code "18") (name "BUTTON4") (class "Default")
      (node (ref "C14") (pin "P$1") (pinfunction "1_P$1") (pintype "passive"))
      (node (ref "R11") (pin "P$2") (pinfunction "2_P$2") (pintype "passive"))
    )
    (net (code "19") (name "BUTTON5") (class "Default")
      (node (ref "C15") (pin "P$1") (pinfunction "1_P$1") (pintype "passive"))
      (node (ref "R12") (pin "P$2") (pinfunction "2_P$2") (pintype "passive"))
      (node (ref "U1") (pin "29") (pinfunction "PB5(OC1A/ADC12/~{OC4B})_29") (pintype "bidirectional"))
    )
    (net (code "20") (name "BUTTON6") (class "Default")
      (node (ref "C16") (pin "P$1") (pinfunction "1_P$1") (pintype "passive"))
      (node (ref "R14") (pin "P$2") (pinfunction "2_P$2") (pintype "passive"))
      (node (ref "U1") (pin "30") (pinfunction "PB6(OC1B/OC4B/ADC13)_30") (pintype "bidirectional"))
    )
    (net (code "21") (name "BUTTON7") (class "Default")
      (node (ref "C17") (pin "P$1") (pinfunction "1_P$1") (pintype "passive"))
      (node (ref "R15") (pin "P$2") (pinfunction "2_P$2") (pintype "passive"))
      (node (ref "U1") (pin "12") (pinfunction "PB7(OC0A/OC1C/RTS)_12") (pintype "bidirectional"))
    )
    (net (code "22") (name "BUTTON8") (class "Default")
      (node (ref "C18") (pin "P$1") (pinfunction "1_P$1") (pintype "passive"))
      (node (ref "R19") (pin "P$2") (pinfunction "2_P$2") (pintype "passive"))
      (node (ref "U1") (pin "32") (pinfunction "PC7(ICP3/CLK0/OC4A)_32") (pintype "bidirectional"))
    )
    (net (code "23") (name "CLK_3V3") (class "Default")
      (node (ref "TP1") (pin "P$1") (pinfunction "P$1_P$1") (pintype "bidirectional"))
      (node (ref "U2") (pin "2") (pinfunction "SCK_2") (pintype "bidirectional"))
      (node (ref "U4") (pin "7") (pinfunction "B1_7") (pintype "bidirectional"))
      (node (ref "X11") (pin "5") (pinfunction "CLK_5") (pintype "bidirectional"))
    )
    (net (code "24") (name "CLK_5V") (class "Default")
      (node (ref "TP15") (pin "P$1") (pinfunction "P$1_P$1") (pintype "bidirectional"))
      (node (ref "TP2") (pin "P$1") (pinfunction "P$1_P$1") (pintype "bidirectional"))
      (node (ref "U1") (pin "9") (pinfunction "PB1(SCK)_9") (pintype "bidirectional"))
      (node (ref "U4") (pin "2") (pinfunction "A1_2") (pintype "bidirectional"))
      (node (ref "X2") (pin "3") (pinfunction "SCK_3") (pintype "output"))
    )
    (net (code "25") (name "GND") (class "Default")
      (node (ref "C1") (pin "P$2") (pinfunction "2_P$2") (pintype "passive"))
      (node (ref "C10") (pin "P$2") (pinfunction "2_P$2") (pintype "passive"))
      (node (ref "C11") (pin "P$2") (pinfunction "2_P$2") (pintype "passive"))
      (node (ref "C12") (pin "P$2") (pinfunction "2_P$2") (pintype "passive"))
      (node (ref "C13") (pin "P$2") (pinfunction "2_P$2") (pintype "passive"))
      (node (ref "C14") (pin "P$2") (pinfunction "2_P$2") (pintype "passive"))
      (node (ref "C15") (pin "P$2") (pinfunction "2_P$2") (pintype "passive"))
      (node (ref "C16") (pin "P$2") (pinfunction "2_P$2") (pintype "passive"))
      (node (ref "C17") (pin "P$2") (pinfunction "2_P$2") (pintype "passive"))
      (node (ref "C18") (pin "P$2") (pinfunction "2_P$2") (pintype "passive"))
      (node (ref "C19") (pin "P$1") (pinfunction "1_P$1") (pintype "passive"))
      (node (ref "C2") (pin "P$2") (pinfunction "2_P$2") (pintype "passive"))
      (node (ref "C20") (pin "P$1") (pinfunction "1_P$1") (pintype "passive"))
      (node (ref "C21") (pin "P$1") (pinfunction "1_P$1") (pintype "passive"))
      (node (ref "C22") (pin "P$2") (pinfunction "2_P$2") (pintype "passive"))
      (node (ref "C23") (pin "P$2") (pinfunction "2_P$2") (pintype "passive"))
      (node (ref "C24") (pin "P$2") (pinfunction "2_P$2") (pintype "passive"))
      (node (ref "C25") (pin "P$2") (pinfunction "2_P$2") (pintype "passive"))
      (node (ref "C26") (pin "P$2") (pinfunction "2_P$2") (pintype "passive"))
      (node (ref "C27") (pin "P$2") (pinfunction "2_P$2") (pintype "passive"))
      (node (ref "C28") (pin "P$2") (pinfunction "2_P$2") (pintype "passive"))
      (node (ref "C29") (pin "P$2") (pinfunction "2_P$2") (pintype "passive"))
      (node (ref "C3") (pin "P$2") (pinfunction "2_P$2") (pintype "passive"))
      (node (ref "C30") (pin "P$1") (pinfunction "1_P$1") (pintype "passive"))
      (node (ref "C31") (pin "P$2") (pinfunction "2_P$2") (pintype "passive"))
      (node (ref "C32") (pin "P$2") (pinfunction "2_P$2") (pintype "passive"))
      (node (ref "C33") (pin "P$1") (pinfunction "1_P$1") (pintype "passive"))
      (node (ref "C34") (pin "P$2") (pinfunction "2_P$2") (pintype "passive"))
      (node (ref "C4") (pin "P$2") (pinfunction "2_P$2") (pintype "passive"))
      (node (ref "C44") (pin "P$2") (pinfunction "2_P$2") (pintype "passive"))
      (node (ref "C46") (pin "P$1") (pinfunction "1_P$1") (pintype "passive"))
      (node (ref "C48") (pin "P$2") (pinfunction "2_P$2") (pintype "passive"))
      (node (ref "C5") (pin "P$2") (pinfunction "2_P$2") (pintype "passive"))
      (node (ref "C6") (pin "P$2") (pinfunction "2_P$2") (pintype "passive"))
      (node (ref "C7") (pin "P$2") (pinfunction "2_P$2") (pintype "passive"))
      (node (ref "C9") (pin "P$1") (pinfunction "1_P$1") (pintype "passive"))
      (node (ref "D2") (pin "A") (pinfunction "A_A") (pintype "passive"))
      (node (ref "D27") (pin "C") (pinfunction "CATHODE_C") (pintype "passive"))
      (node (ref "D3") (pin "C") (pinfunction "CATHODE_C") (pintype "passive"))
      (node (ref "D4") (pin "C") (pinfunction "CATHODE_C") (pintype "passive"))
      (node (ref "FB2") (pin "P$1") (pinfunction "1_P$1") (pintype "passive"))
      (node (ref "FB4") (pin "P$1") (pinfunction "1_P$1") (pintype "passive"))
      (node (ref "R24") (pin "P$2") (pinfunction "2_P$2") (pintype "passive"))
      (node (ref "R7") (pin "P$2") (pinfunction "2_P$2") (pintype "passive"))
      (node (ref "S1") (pin "1") (pinfunction "P$1_1") (pintype "bidirectional"))
      (node (ref "S10") (pin "3") (pinfunction "P$2_3") (pintype "bidirectional"))
      (node (ref "S3") (pin "1") (pinfunction "P$1_1") (pintype "bidirectional"))
      (node (ref "S4") (pin "1") (pinfunction "P$1_1") (pintype "bidirectional"))
      (node (ref "S5") (pin "1") (pinfunction "P$1_1") (pintype "bidirectional"))
      (node (ref "S6") (pin "1") (pinfunction "P$1_1") (pintype "bidirectional"))
      (node (ref "S7") (pin "1") (pinfunction "P$1_1") (pintype "bidirectional"))
      (node (ref "S8") (pin "1") (pinfunction "P$1_1") (pintype "bidirectional"))
      (node (ref "S9") (pin "1") (pinfunction "P$1_1") (pintype "bidirectional"))
      (node (ref "U1") (pin "15") (pinfunction "GND_15") (pintype "bidirectional"))
      (node (ref "U1") (pin "23") (pinfunction "GND1_23") (pintype "bidirectional"))
      (node (ref "U1") (pin "35") (pinfunction "GND2_35") (pintype "bidirectional"))
      (node (ref "U1") (pin "43") (pinfunction "GND3_43") (pintype "bidirectional"))
      (node (ref "U2") (pin "7") (pinfunction "GND_7") (pintype "bidirectional"))
      (node (ref "U3") (pin "1") (pinfunction "GND_1") (pintype "passive"))
      (node (ref "U4") (pin "4") (pinfunction "GND_4") (pintype "power_in"))
      (node (ref "U5") (pin "4") (pinfunction "GND_4") (pintype "power_in"))
      (node (ref "U5") (pin "5") (pinfunction "DIR_5") (pintype "input"))
      (node (ref "U6") (pin "4") (pinfunction "GND_4") (pintype "power_in"))
      (node (ref "X11") (pin "6") (pinfunction "VSS_6") (pintype "bidirectional"))
      (node (ref "X11") (pin "DET_LVR") (pinfunction "LAT_DET_LVR") (pintype "bidirectional"))
      (node (ref "X13") (pin "P$1") (pinfunction "P$1_P$1") (pintype "bidirectional"))
      (node (ref "X13") (pin "P$2") (pinfunction "P$2_P$2") (pintype "bidirectional"))
      (node (ref "X14") (pin "4") (pinfunction "4_4") (pintype "passive"))
      (node (ref "X15") (pin "8") (pinfunction "8_8") (pintype "passive"))
      (node (ref "X2") (pin "6") (pinfunction "GND_6") (pintype "input"))
      (node (ref "X3") (pin "4") (pinfunction "4_4") (pintype "passive"))
    )
    (net (code "26") (name "GND_E") (class "Default")
      (node (ref "FB2") (pin "P$2") (pinfunction "2_P$2") (pintype "passive"))
      (node (ref "X1") (pin "G1") (pinfunction "TAB_G1") (pintype "bidirectional"))
      (node (ref "X1") (pin "G2") (pinfunction "TAB_G2") (pintype "bidirectional"))
      (node (ref "X1") (pin "H1") (pinfunction "TAB_H1") (pintype "bidirectional"))
      (node (ref "X1") (pin "H2") (pinfunction "TAB_H2") (pintype "bidirectional"))
      (node (ref "X1") (pin "H3") (pinfunction "TAB_H3") (pintype "bidirectional"))
      (node (ref "X1") (pin "H4") (pinfunction "TAB_H4") (pintype "bidirectional"))
      (node (ref "X11") (pin "H1") (pinfunction "GND1_H1") (pintype "bidirectional"))
      (node (ref "X11") (pin "H2") (pinfunction "GND2_H2") (pintype "bidirectional"))
      (node (ref "X11") (pin "H3") (pinfunction "GND3_H3") (pintype "bidirectional"))
      (node (ref "X11") (pin "H4") (pinfunction "GND4_H4") (pintype "bidirectional"))
    )
    (net (code "27") (name "INTERRUPT7") (class "Default")
      (node (ref "R31") (pin "P$2") (pinfunction "2_P$2") (pintype "passive"))
      (node (ref "U1") (pin "1") (pinfunction "PE6(INT.6/AIN0)_1") (pintype "bidirectional"))
    )
    (net (code "28") (name "MISO_3V3") (class "Default")
      (node (ref "U2") (pin "8") (pinfunction "MISO_8") (pintype "bidirectional"))
      (node (ref "U5") (pin "7") (pinfunction "B1_7") (pintype "bidirectional"))
      (node (ref "X11") (pin "7") (pinfunction "DAT0_7") (pintype "bidirectional"))
    )
    (net (code "29") (name "MISO_5V") (class "Default")
      (node (ref "TP16") (pin "P$1") (pinfunction "P$1_P$1") (pintype "bidirectional"))
      (node (ref "U1") (pin "11") (pinfunction "PB3(PDO/MISO)_11") (pintype "bidirectional"))
      (node (ref "U5") (pin "2") (pinfunction "A1_2") (pintype "bidirectional"))
      (node (ref "X2") (pin "1") (pinfunction "MISO_1") (pintype "input"))
    )
    (net (code "30") (name "MOSI_3V3") (class "Default")
      (node (ref "U2") (pin "1") (pinfunction "MOSI_1") (pintype "bidirectional"))
      (node (ref "U4") (pin "6") (pinfunction "B2_6") (pintype "bidirectional"))
      (node (ref "X11") (pin "3") (pinfunction "CMD_3") (pintype "bidirectional"))
    )
    (net (code "31") (name "MOSI_5V") (class "Default")
      (node (ref "TP17") (pin "P$1") (pinfunction "P$1_P$1") (pintype "bidirectional"))
      (node (ref "U1") (pin "10") (pinfunction "PB2(PDI/MOSI)_10") (pintype "bidirectional"))
      (node (ref "U4") (pin "3") (pinfunction "A2_3") (pintype "bidirectional"))
      (node (ref "X2") (pin "4") (pinfunction "MOSI_4") (pintype "output"))
    )
    (net (code "32") (name "Net-(C1-1)") (class "Default")
      (node (ref "C1") (pin "P$1") (pinfunction "1_P$1") (pintype "passive"))
      (node (ref "R6") (pin "P$1") (pinfunction "1_P$1") (pintype "passive"))
      (node (ref "U1") (pin "17") (pinfunction "XTAL1_17") (pintype "bidirectional"))
      (node (ref "Y1") (pin "2") (pinfunction "2_2") (pintype "passive"))
    )
    (net (code "33") (name "Net-(C2-1)") (class "Default")
      (node (ref "C2") (pin "P$1") (pinfunction "1_P$1") (pintype "passive"))
      (node (ref "R6") (pin "P$2") (pinfunction "2_P$2") (pintype "passive"))
      (node (ref "U1") (pin "16") (pinfunction "XTAL2_16") (pintype "bidirectional"))
      (node (ref "Y1") (pin "1") (pinfunction "1_1") (pintype "passive"))
    )
    (net (code "34") (name "Net-(C7-1)") (class "Default")
      (node (ref "C7") (pin "P$1") (pinfunction "1_P$1") (pintype "passive"))
      (node (ref "FB3") (pin "P$2") (pinfunction "2_P$2") (pintype "passive"))
      (node (ref "U1") (pin "24") (pinfunction "AVCC_24") (pintype "bidirectional"))
      (node (ref "U1") (pin "44") (pinfunction "AVCC1_44") (pintype "bidirectional"))
    )
    (net (code "35") (name "Net-(C8-2)") (class "Default")
      (node (ref "C8") (pin "P$2") (pinfunction "2_P$2") (pintype "passive"))
      (node (ref "U1") (pin "6") (pinfunction "UCAP_6") (pintype "bidirectional"))
    )
    (net (code "36") (name "Net-(D1-Pad1)") (class "Default")
      (node (ref "D1") (pin "1") (pinfunction "1_1") (pintype "bidirectional"))
      (node (ref "L1") (pin "A2") (pinfunction "A2_A2") (pintype "bidirectional"))
      (node (ref "X1") (pin "D+") (pinfunction "D+_D+") (pintype "bidirectional"))
    )
    (net (code "37") (name "Net-(D1-Pad6)") (class "Default")
      (node (ref "D1") (pin "6") (pinfunction "6_6") (pintype "bidirectional"))
      (node (ref "L1") (pin "B2") (pinfunction "B2_B2") (pintype "bidirectional"))
      (node (ref "X1") (pin "D-") (pinfunction "D-_D-") (pintype "bidirectional"))
    )
    (net (code "38") (name "Net-(D3-ANODE)") (class "Default")
      (node (ref "D3") (pin "A") (pinfunction "ANODE_A") (pintype "passive"))
      (node (ref "R23") (pin "P$1") (pinfunction "1_P$1") (pintype "passive"))
    )
    (net (code "39") (name "Net-(D4-ANODE)") (class "Default")
      (node (ref "D4") (pin "A") (pinfunction "ANODE_A") (pintype "passive"))
      (node (ref "R18") (pin "P$1") (pinfunction "1_P$1") (pintype "passive"))
    )
    (net (code "40") (name "Net-(D27-ANODE)") (class "Default")
      (node (ref "D27") (pin "A") (pinfunction "ANODE_A") (pintype "passive"))
      (node (ref "R13") (pin "P$1") (pinfunction "1_P$1") (pintype "passive"))
    )
    (net (code "41") (name "Net-(FB6-1)") (class "Default")
      (node (ref "FB6") (pin "P$1") (pinfunction "1_P$1") (pintype "passive"))
      (node (ref "X15") (pin "1") (pinfunction "1_1") (pintype "passive"))
    )
    (net (code "42") (name "Net-(R2-2)") (class "Default")
      (node (ref "R2") (pin "P$2") (pinfunction "2_P$2") (pintype "passive"))
      (node (ref "X3") (pin "2") (pinfunction "2_2") (pintype "passive"))
    )
    (net (code "43") (name "Net-(R3-2)") (class "Default")
      (node (ref "R3") (pin "P$2") (pinfunction "2_P$2") (pintype "passive"))
      (node (ref "X3") (pin "3") (pinfunction "3_3") (pintype "passive"))
    )
    (net (code "44") (name "Net-(R4-1)") (class "Default")
      (node (ref "L1") (pin "A1") (pinfunction "A1_A1") (pintype "bidirectional"))
      (node (ref "R4") (pin "P$1") (pinfunction "1_P$1") (pintype "passive"))
    )
    (net (code "45") (name "Net-(R5-1)") (class "Default")
      (node (ref "L1") (pin "B1") (pinfunction "B1_B1") (pintype "bidirectional"))
      (node (ref "R5") (pin "P$1") (pinfunction "1_P$1") (pintype "passive"))
    )
    (net (code "46") (name "Net-(R7-1)") (class "Default")
      (node (ref "R7") (pin "P$1") (pinfunction "1_P$1") (pintype "passive"))
      (node (ref "U1") (pin "33") (pinfunction "PE2(~{HWB})_33") (pintype "bidirectional"))
    )
    (net (code "47") (name "Net-(R8-1)") (class "Default")
      (node (ref "R8") (pin "P$1") (pinfunction "1_P$1") (pintype "passive"))
      (node (ref "S1") (pin "2") (pinfunction "P$2_2") (pintype "bidirectional"))
    )
    (net (code "48") (name "Net-(R9-1)") (class "Default")
      (node (ref "R9") (pin "P$1") (pinfunction "1_P$1") (pintype "passive"))
      (node (ref "S3") (pin "2") (pinfunction "P$2_2") (pintype "bidirectional"))
    )
    (net (code "49") (name "Net-(R10-1)") (class "Default")
      (node (ref "R10") (pin "P$1") (pinfunction "1_P$1") (pintype "passive"))
      (node (ref "S4") (pin "2") (pinfunction "P$2_2") (pintype "bidirectional"))
    )
    (net (code "50") (name "Net-(R11-1)") (class "Default")
      (node (ref "R11") (pin "P$1") (pinfunction "1_P$1") (pintype "passive"))
      (node (ref "S5") (pin "2") (pinfunction "P$2_2") (pintype "bidirectional"))
    )
    (net (code "51") (name "Net-(R12-1)") (class "Default")
      (node (ref "R12") (pin "P$1") (pinfunction "1_P$1") (pintype "passive"))
      (node (ref "S6") (pin "2") (pinfunction "P$2_2") (pintype "bidirectional"))
    )
    (net (code "52") (name "Net-(R14-1)") (class "Default")
      (node (ref "R14") (pin "P$1") (pinfunction "1_P$1") (pintype "passive"))
      (node (ref "S7") (pin "2") (pinfunction "P$2_2") (pintype "bidirectional"))
    )
    (net (code "53") (name "Net-(R15-1)") (class "Default")
      (node (ref "R15") (pin "P$1") (pinfunction "1_P$1") (pintype "passive"))
      (node (ref "S8") (pin "2") (pinfunction "P$2_2") (pintype "bidirectional"))
    )
    (net (code "54") (name "Net-(R16-1)") (class "Default")
      (node (ref "R16") (pin "P$1") (pinfunction "1_P$1") (pintype "passive"))
      (node (ref "X2") (pin "2") (pinfunction "VCC_2") (pintype "input"))
    )
    (net (code "55") (name "Net-(R17-1)") (class "Default")
      (node (ref "R17") (pin "P$1") (pinfunction "1_P$1") (pintype "passive"))
      (node (ref "R21") (pin "P$1") (pinfunction "1_P$1") (pintype "passive"))
      (node (ref "X14") (pin "1") (pinfunction "1_1") (pintype "passive"))
    )
    (net (code "56") (name "Net-(R19-1)") (class "Default")
      (node (ref "R19") (pin "P$1") (pinfunction "1_P$1") (pintype "passive"))
      (node (ref "S9") (pin "2") (pinfunction "P$2_2") (pintype "bidirectional"))
    )
    (net (code "57") (name "Net-(R20-1)") (class "Default")
      (node (ref "R20") (pin "P$1") (pinfunction "1_P$1") (pintype "passive"))
      (node (ref "R22") (pin "P$1") (pinfunction "1_P$1") (pintype "passive"))
      (node (ref "X14") (pin "2") (pinfunction "2_2") (pintype "passive"))
    )
    (net (code "58") (name "Net-(R24-1)") (class "Default")
      (node (ref "R24") (pin "P$1") (pinfunction "1_P$1") (pintype "passive"))
      (node (ref "U5") (pin "6") (pinfunction "B2_6") (pintype "bidirectional"))
    )
    (net (code "59") (name "Net-(R25-1)") (class "Default")
      (node (ref "R25") (pin "P$1") (pinfunction "1_P$1") (pintype "passive"))
      (node (ref "X15") (pin "2") (pinfunction "2_2") (pintype "passive"))
    )
    (net (code "60") (name "Net-(R26-1)") (class "Default")
      (node (ref "R26") (pin "P$1") (pinfunction "1_P$1") (pintype "passive"))
      (node (ref "X15") (pin "3") (pinfunction "3_3") (pintype "passive"))
    )
    (net (code "61") (name "Net-(R27-1)") (class "Default")
      (node (ref "R27") (pin "P$1") (pinfunction "1_P$1") (pintype "passive"))
      (node (ref "X15") (pin "4") (pinfunction "4_4") (pintype "passive"))
    )
    (net (code "62") (name "Net-(R28-1)") (class "Default")
      (node (ref "R28") (pin "P$1") (pinfunction "1_P$1") (pintype "passive"))
      (node (ref "X15") (pin "5") (pinfunction "5_5") (pintype "passive"))
    )
    (net (code "63") (name "Net-(R29-1)") (class "Default")
      (node (ref "R29") (pin "P$1") (pinfunction "1_P$1") (pintype "passive"))
      (node (ref "X15") (pin "6") (pinfunction "6_6") (pintype "passive"))
    )
    (net (code "64") (name "Net-(R30-1)") (class "Default")
      (node (ref "R30") (pin "P$1") (pinfunction "1_P$1") (pintype "passive"))
      (node (ref "X15") (pin "7") (pinfunction "7_7") (pintype "passive"))
    )
    (net (code "65") (name "Net-(R31-1)") (class "Default")
      (node (ref "R31") (pin "P$1") (pinfunction "1_P$1") (pintype "passive"))
      (node (ref "X14") (pin "3") (pinfunction "3_3") (pintype "passive"))
    )
    (net (code "66") (name "Net-(R33-1)") (class "Default")
      (node (ref "R33") (pin "P$1") (pinfunction "1_P$1") (pintype "passive"))
      (node (ref "U2") (pin "5") (pinfunction "~{WP}_5") (pintype "bidirectional"))
    )
    (net (code "67") (name "RXD") (class "Default")
      (node (ref "R2") (pin "P$1") (pinfunction "1_P$1") (pintype "passive"))
      (node (ref "U1") (pin "20") (pinfunction "PD2(INT2/RXD1)_20") (pintype "bidirectional"))
    )
    (net (code "68") (name "RX_LED") (class "Default")
      (node (ref "R13") (pin "P$2") (pinfunction "2_P$2") (pintype "passive"))
      (node (ref "U1") (pin "8") (pinfunction "PB0(SS)_8") (pintype "bidirectional"))
    )
    (net (code "69") (name "SCL_5V") (class "Default")
      (node (ref "R21") (pin "P$2") (pinfunction "2_P$2") (pintype "passive"))
      (node (ref "U1") (pin "18") (pinfunction "PD0(INT0/OC0B/SCL)_18") (pintype "bidirectional"))
    )
    (net (code "70") (name "SDA_5V") (class "Default")
      (node (ref "R22") (pin "P$2") (pinfunction "2_P$2") (pintype "passive"))
      (node (ref "U1") (pin "19") (pinfunction "PD1(INT1/SDA)_19") (pintype "bidirectional"))
    )
    (net (code "71") (name "SD_DETECT") (class "Default")
      (node (ref "X11") (pin "DET_SW") (pinfunction "SW_DET_SW") (pintype "bidirectional"))
    )
    (net (code "72") (name "TXD") (class "Default")
      (node (ref "R3") (pin "P$1") (pinfunction "1_P$1") (pintype "passive"))
      (node (ref "U1") (pin "21") (pinfunction "PD3(INT3/TXD1)_21") (pintype "bidirectional"))
    )
    (net (code "73") (name "TX_LED") (class "Default")
      (node (ref "R18") (pin "P$2") (pinfunction "2_P$2") (pintype "passive"))
      (node (ref "U1") (pin "22") (pinfunction "PD5(XCK/CTS)_22") (pintype "bidirectional"))
    )
    (net (code "74") (name "USB_D+") (class "Default")
      (node (ref "R4") (pin "P$2") (pinfunction "2_P$2") (pintype "passive"))
      (node (ref "U1") (pin "4") (pinfunction "D+_4") (pintype "bidirectional"))
    )
    (net (code "75") (name "USB_D-") (class "Default")
      (node (ref "R5") (pin "P$2") (pinfunction "2_P$2") (pintype "passive"))
      (node (ref "U1") (pin "3") (pinfunction "D-_3") (pintype "bidirectional"))
    )
    (net (code "76") (name "USB_GND") (class "Default")
      (node (ref "C8") (pin "P$1") (pinfunction "1_P$1") (pintype "passive"))
      (node (ref "D1") (pin "2") (pinfunction "V-_2") (pintype "bidirectional"))
      (node (ref "FB4") (pin "P$2") (pinfunction "2_P$2") (pintype "passive"))
      (node (ref "U1") (pin "5") (pinfunction "UGND_5") (pintype "bidirectional"))
      (node (ref "X1") (pin "GND") (pinfunction "GND_GND") (pintype "bidirectional"))
    )
    (net (code "77") (name "USB_ID") (class "Default")
      (node (ref "X1") (pin "ID") (pinfunction "ID_ID") (pintype "bidirectional"))
    )
    (net (code "78") (name "USB_VBUS") (class "Default")
      (node (ref "FB1") (pin "P$1") (pinfunction "1_P$1") (pintype "passive"))
      (node (ref "U1") (pin "7") (pinfunction "VBUS_7") (pintype "bidirectional"))
      (node (ref "X1") (pin "VBUS") (pinfunction "V+_VBUS") (pintype "bidirectional"))
    )
    (net (code "79") (name "unconnected-(D1-Pad3)") (class "Default")
      (node (ref "D1") (pin "3") (pinfunction "3_3") (pintype "bidirectional"))
    )
    (net (code "80") (name "unconnected-(D1-Pad4)") (class "Default")
      (node (ref "D1") (pin "4") (pinfunction "4_4") (pintype "bidirectional"))
    )
    (net (code "81") (name "unconnected-(U1-AREF-Pad42)") (class "Default")
      (node (ref "U1") (pin "42") (pinfunction "AREF_42") (pintype "bidirectional"))
    )
    (net (code "82") (name "unconnected-(U5-A2-Pad3)") (class "Default")
      (node (ref "U5") (pin "3") (pinfunction "A2_3") (pintype "bidirectional"))
    )
    (net (code "83") (name "unconnected-(X11-DAT1-Pad8)") (class "Default")
      (node (ref "X11") (pin "8") (pinfunction "DAT1_8") (pintype "bidirectional"))
    )
    (net (code "84") (name "unconnected-(X11-DAT2-Pad1)") (class "Default")
      (node (ref "X11") (pin "1") (pinfunction "DAT2_1") (pintype "bidirectional"))
    )
  )
)
